# untitled.net
KiCad netlist of a schematic drawn in EAGLE
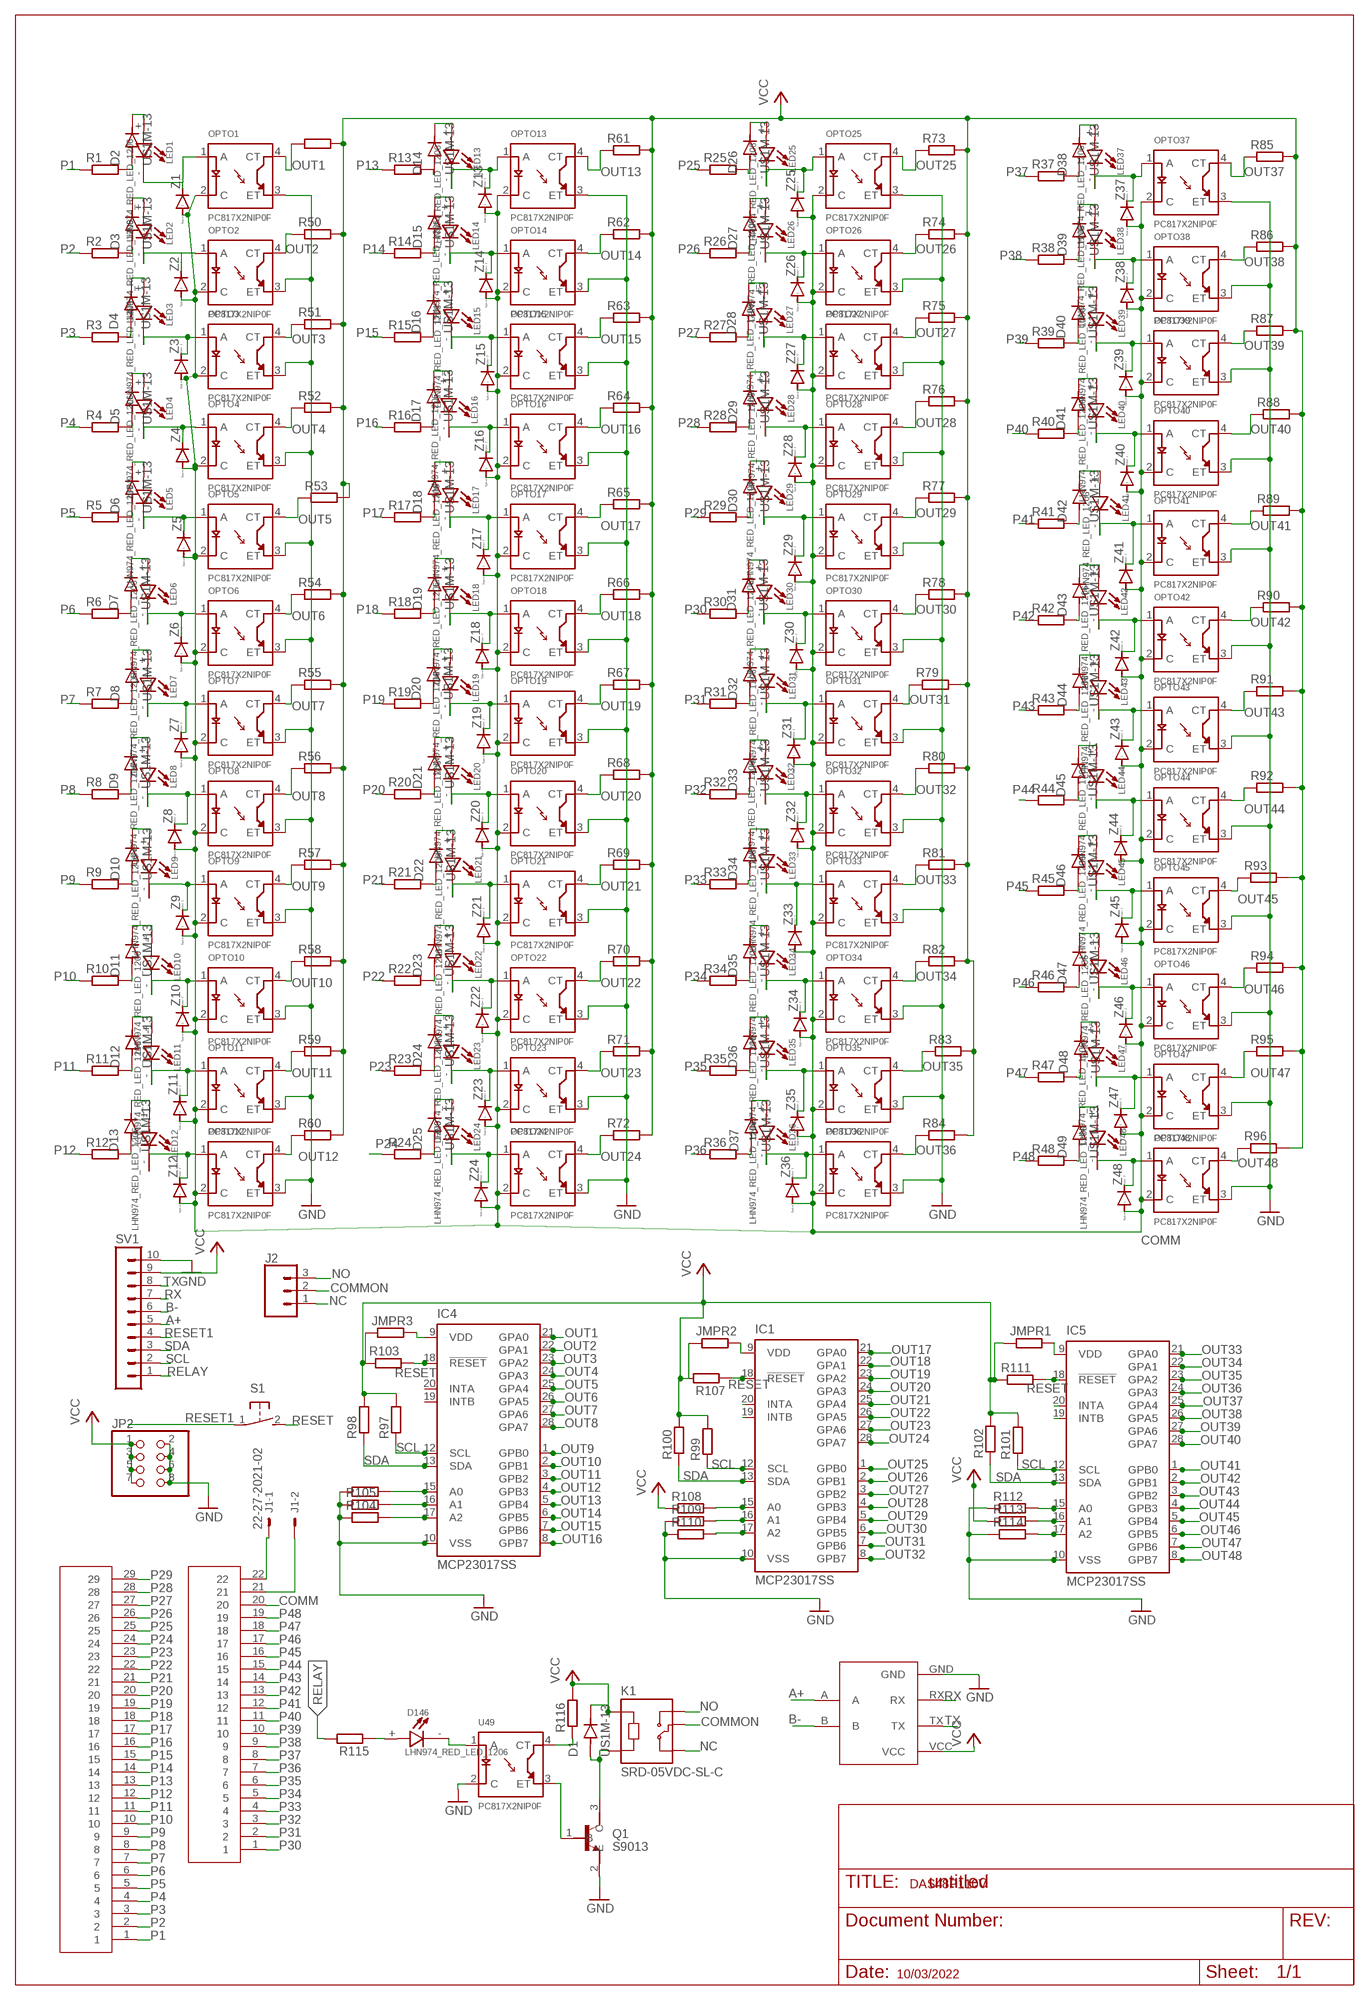
[diagram p0: schematic, sheet 1]

(export (version "E")
  (design (tool "Eeschema 10.0.6"))
  (components
    (comp (ref "D1")
      (value "US1M-13")
      (footprint "eagle-import:DIOM5226X240N")
      (fields (field (name "MF") "Diodes Incorporated"))
      (libsource (lib "eagle-import") (part "US1M-13"))
    )
    (comp (ref "D2")
      (value "US1M-13")
      (footprint "eagle-import:DIOM5226X240N")
      (fields (field (name "MF") "Diodes Incorporated"))
      (libsource (lib "eagle-import") (part "US1M-13"))
    )
    (comp (ref "D3")
      (value "US1M-13")
      (footprint "eagle-import:DIOM5226X240N")
      (fields (field (name "MF") "Diodes Incorporated"))
      (libsource (lib "eagle-import") (part "US1M-13"))
    )
    (comp (ref "D4")
      (value "US1M-13")
      (footprint "eagle-import:DIOM5226X240N")
      (fields (field (name "MF") "Diodes Incorporated"))
      (libsource (lib "eagle-import") (part "US1M-13"))
    )
    (comp (ref "D5")
      (value "US1M-13")
      (footprint "eagle-import:DIOM5226X240N")
      (fields (field (name "MF") "Diodes Incorporated"))
      (libsource (lib "eagle-import") (part "US1M-13"))
    )
    (comp (ref "D6")
      (value "US1M-13")
      (footprint "eagle-import:DIOM5226X240N")
      (fields (field (name "MF") "Diodes Incorporated"))
      (libsource (lib "eagle-import") (part "US1M-13"))
    )
    (comp (ref "D7")
      (value "US1M-13")
      (footprint "eagle-import:DIOM5226X240N")
      (fields (field (name "MF") "Diodes Incorporated"))
      (libsource (lib "eagle-import") (part "US1M-13"))
    )
    (comp (ref "D8")
      (value "US1M-13")
      (footprint "eagle-import:DIOM5226X240N")
      (fields (field (name "MF") "Diodes Incorporated"))
      (libsource (lib "eagle-import") (part "US1M-13"))
    )
    (comp (ref "D9")
      (value "US1M-13")
      (footprint "eagle-import:DIOM5226X240N")
      (fields (field (name "MF") "Diodes Incorporated"))
      (libsource (lib "eagle-import") (part "US1M-13"))
    )
    (comp (ref "D10")
      (value "US1M-13")
      (footprint "eagle-import:DIOM5226X240N")
      (fields (field (name "MF") "Diodes Incorporated"))
      (libsource (lib "eagle-import") (part "US1M-13"))
    )
    (comp (ref "D11")
      (value "US1M-13")
      (footprint "eagle-import:DIOM5226X240N")
      (fields (field (name "MF") "Diodes Incorporated"))
      (libsource (lib "eagle-import") (part "US1M-13"))
    )
    (comp (ref "D12")
      (value "US1M-13")
      (footprint "eagle-import:DIOM5226X240N")
      (fields (field (name "MF") "Diodes Incorporated"))
      (libsource (lib "eagle-import") (part "US1M-13"))
    )
    (comp (ref "D13")
      (value "US1M-13")
      (footprint "eagle-import:DIOM5226X240N")
      (fields (field (name "MF") "Diodes Incorporated"))
      (libsource (lib "eagle-import") (part "US1M-13"))
    )
    (comp (ref "D14")
      (value "US1M-13")
      (footprint "eagle-import:DIOM5226X240N")
      (fields (field (name "MF") "Diodes Incorporated"))
      (libsource (lib "eagle-import") (part "US1M-13"))
    )
    (comp (ref "D15")
      (value "US1M-13")
      (footprint "eagle-import:DIOM5226X240N")
      (fields (field (name "MF") "Diodes Incorporated"))
      (libsource (lib "eagle-import") (part "US1M-13"))
    )
    (comp (ref "D16")
      (value "US1M-13")
      (footprint "eagle-import:DIOM5226X240N")
      (fields (field (name "MF") "Diodes Incorporated"))
      (libsource (lib "eagle-import") (part "US1M-13"))
    )
    (comp (ref "D17")
      (value "US1M-13")
      (footprint "eagle-import:DIOM5226X240N")
      (fields (field (name "MF") "Diodes Incorporated"))
      (libsource (lib "eagle-import") (part "US1M-13"))
    )
    (comp (ref "D18")
      (value "US1M-13")
      (footprint "eagle-import:DIOM5226X240N")
      (fields (field (name "MF") "Diodes Incorporated"))
      (libsource (lib "eagle-import") (part "US1M-13"))
    )
    (comp (ref "D19")
      (value "US1M-13")
      (footprint "eagle-import:DIOM5226X240N")
      (fields (field (name "MF") "Diodes Incorporated"))
      (libsource (lib "eagle-import") (part "US1M-13"))
    )
    (comp (ref "D20")
      (value "US1M-13")
      (footprint "eagle-import:DIOM5226X240N")
      (fields (field (name "MF") "Diodes Incorporated"))
      (libsource (lib "eagle-import") (part "US1M-13"))
    )
    (comp (ref "D21")
      (value "US1M-13")
      (footprint "eagle-import:DIOM5226X240N")
      (fields (field (name "MF") "Diodes Incorporated"))
      (libsource (lib "eagle-import") (part "US1M-13"))
    )
    (comp (ref "D22")
      (value "US1M-13")
      (footprint "eagle-import:DIOM5226X240N")
      (fields (field (name "MF") "Diodes Incorporated"))
      (libsource (lib "eagle-import") (part "US1M-13"))
    )
    (comp (ref "D23")
      (value "US1M-13")
      (footprint "eagle-import:DIOM5226X240N")
      (fields (field (name "MF") "Diodes Incorporated"))
      (libsource (lib "eagle-import") (part "US1M-13"))
    )
    (comp (ref "D24")
      (value "US1M-13")
      (footprint "eagle-import:DIOM5226X240N")
      (fields (field (name "MF") "Diodes Incorporated"))
      (libsource (lib "eagle-import") (part "US1M-13"))
    )
    (comp (ref "D25")
      (value "US1M-13")
      (footprint "eagle-import:DIOM5226X240N")
      (fields (field (name "MF") "Diodes Incorporated"))
      (libsource (lib "eagle-import") (part "US1M-13"))
    )
    (comp (ref "D26")
      (value "US1M-13")
      (footprint "eagle-import:DIOM5226X240N")
      (fields (field (name "MF") "Diodes Incorporated"))
      (libsource (lib "eagle-import") (part "US1M-13"))
    )
    (comp (ref "D27")
      (value "US1M-13")
      (footprint "eagle-import:DIOM5226X240N")
      (fields (field (name "MF") "Diodes Incorporated"))
      (libsource (lib "eagle-import") (part "US1M-13"))
    )
    (comp (ref "D28")
      (value "US1M-13")
      (footprint "eagle-import:DIOM5226X240N")
      (fields (field (name "MF") "Diodes Incorporated"))
      (libsource (lib "eagle-import") (part "US1M-13"))
    )
    (comp (ref "D29")
      (value "US1M-13")
      (footprint "eagle-import:DIOM5226X240N")
      (fields (field (name "MF") "Diodes Incorporated"))
      (libsource (lib "eagle-import") (part "US1M-13"))
    )
    (comp (ref "D30")
      (value "US1M-13")
      (footprint "eagle-import:DIOM5226X240N")
      (fields (field (name "MF") "Diodes Incorporated"))
      (libsource (lib "eagle-import") (part "US1M-13"))
    )
    (comp (ref "D31")
      (value "US1M-13")
      (footprint "eagle-import:DIOM5226X240N")
      (fields (field (name "MF") "Diodes Incorporated"))
      (libsource (lib "eagle-import") (part "US1M-13"))
    )
    (comp (ref "D32")
      (value "US1M-13")
      (footprint "eagle-import:DIOM5226X240N")
      (fields (field (name "MF") "Diodes Incorporated"))
      (libsource (lib "eagle-import") (part "US1M-13"))
    )
    (comp (ref "D33")
      (value "US1M-13")
      (footprint "eagle-import:DIOM5226X240N")
      (fields (field (name "MF") "Diodes Incorporated"))
      (libsource (lib "eagle-import") (part "US1M-13"))
    )
    (comp (ref "D34")
      (value "US1M-13")
      (footprint "eagle-import:DIOM5226X240N")
      (fields (field (name "MF") "Diodes Incorporated"))
      (libsource (lib "eagle-import") (part "US1M-13"))
    )
    (comp (ref "D35")
      (value "US1M-13")
      (footprint "eagle-import:DIOM5226X240N")
      (fields (field (name "MF") "Diodes Incorporated"))
      (libsource (lib "eagle-import") (part "US1M-13"))
    )
    (comp (ref "D36")
      (value "US1M-13")
      (footprint "eagle-import:DIOM5226X240N")
      (fields (field (name "MF") "Diodes Incorporated"))
      (libsource (lib "eagle-import") (part "US1M-13"))
    )
    (comp (ref "D37")
      (value "US1M-13")
      (footprint "eagle-import:DIOM5226X240N")
      (fields (field (name "MF") "Diodes Incorporated"))
      (libsource (lib "eagle-import") (part "US1M-13"))
    )
    (comp (ref "D38")
      (value "US1M-13")
      (footprint "eagle-import:DIOM5226X240N")
      (fields (field (name "MF") "Diodes Incorporated"))
      (libsource (lib "eagle-import") (part "US1M-13"))
    )
    (comp (ref "D39")
      (value "US1M-13")
      (footprint "eagle-import:DIOM5226X240N")
      (fields (field (name "MF") "Diodes Incorporated"))
      (libsource (lib "eagle-import") (part "US1M-13"))
    )
    (comp (ref "D40")
      (value "US1M-13")
      (footprint "eagle-import:DIOM5226X240N")
      (fields (field (name "MF") "Diodes Incorporated"))
      (libsource (lib "eagle-import") (part "US1M-13"))
    )
    (comp (ref "D41")
      (value "US1M-13")
      (footprint "eagle-import:DIOM5226X240N")
      (fields (field (name "MF") "Diodes Incorporated"))
      (libsource (lib "eagle-import") (part "US1M-13"))
    )
    (comp (ref "D42")
      (value "US1M-13")
      (footprint "eagle-import:DIOM5226X240N")
      (fields (field (name "MF") "Diodes Incorporated"))
      (libsource (lib "eagle-import") (part "US1M-13"))
    )
    (comp (ref "D43")
      (value "US1M-13")
      (footprint "eagle-import:DIOM5226X240N")
      (fields (field (name "MF") "Diodes Incorporated"))
      (libsource (lib "eagle-import") (part "US1M-13"))
    )
    (comp (ref "D44")
      (value "US1M-13")
      (footprint "eagle-import:DIOM5226X240N")
      (fields (field (name "MF") "Diodes Incorporated"))
      (libsource (lib "eagle-import") (part "US1M-13"))
    )
    (comp (ref "D45")
      (value "US1M-13")
      (footprint "eagle-import:DIOM5226X240N")
      (fields (field (name "MF") "Diodes Incorporated"))
      (libsource (lib "eagle-import") (part "US1M-13"))
    )
    (comp (ref "D46")
      (value "US1M-13")
      (footprint "eagle-import:DIOM5226X240N")
      (fields (field (name "MF") "Diodes Incorporated"))
      (libsource (lib "eagle-import") (part "US1M-13"))
    )
    (comp (ref "D47")
      (value "US1M-13")
      (footprint "eagle-import:DIOM5226X240N")
      (fields (field (name "MF") "Diodes Incorporated"))
      (libsource (lib "eagle-import") (part "US1M-13"))
    )
    (comp (ref "D48")
      (value "US1M-13")
      (footprint "eagle-import:DIOM5226X240N")
      (fields (field (name "MF") "Diodes Incorporated"))
      (libsource (lib "eagle-import") (part "US1M-13"))
    )
    (comp (ref "D49")
      (value "US1M-13")
      (footprint "eagle-import:DIOM5226X240N")
      (fields (field (name "MF") "Diodes Incorporated"))
      (libsource (lib "eagle-import") (part "US1M-13"))
    )
    (comp (ref "D146")
      (value "LHN974_RED_LED_1206")
      (footprint "eagle-import:LEDC3216X120N")
      (fields (field (name "MF") "Osram") (field (name "MP") "LHN974 RED LED 1206"))
      (libsource (lib "eagle-import") (part "LHN974_RED_LED_1206"))
    )
    (comp (ref "HEADER-22P1")
      (value "HEADER-22P")
      (footprint "eagle-import:HEADER-29P")
      (libsource (lib "eagle-import") (part "HEADER-22P"))
    )
    (comp (ref "HEADER-29P1")
      (value "HEADER-29P")
      (footprint "eagle-import:HEADER-29P")
      (libsource (lib "eagle-import") (part "HEADER-29P"))
    )
    (comp (ref "IC1")
      (value "MCP23017SS")
      (footprint "eagle-import:SSOP28DB")
      (libsource (lib "eagle-import") (part "MCP23017SS"))
    )
    (comp (ref "IC4")
      (value "MCP23017SS")
      (footprint "eagle-import:SSOP28DB")
      (libsource (lib "eagle-import") (part "MCP23017SS"))
    )
    (comp (ref "IC5")
      (value "MCP23017SS")
      (footprint "eagle-import:SSOP28DB")
      (libsource (lib "eagle-import") (part "MCP23017SS"))
    )
    (comp (ref "J1")
      (value "22-27-2021-02")
      (footprint "eagle-import:6410-02")
      (fields (field (name "MF") "MOLEX"))
      (libsource (lib "eagle-import") (part "22-?-0227-2021"))
    )
    (comp (ref "J2")
      (value "CONN_03LONGPADS")
      (footprint "eagle-import:1X03_LONGPADS")
      (libsource (lib "eagle-import") (part "CONN_03LONGPADS"))
    )
    (comp (ref "JMPR1")
      (value "R-EU_R0402")
      (footprint "eagle-import:R0402")
      (libsource (lib "eagle-import") (part "R-EU_R0402"))
    )
    (comp (ref "JMPR2")
      (value "R-EU_R0402")
      (footprint "eagle-import:R0402")
      (libsource (lib "eagle-import") (part "R-EU_R0402"))
    )
    (comp (ref "JMPR3")
      (value "R-EU_R0402")
      (footprint "eagle-import:R0402")
      (libsource (lib "eagle-import") (part "R-EU_R0402"))
    )
    (comp (ref "JP2")
      (value "PINHD-2X4")
      (footprint "eagle-import:2X04")
      (libsource (lib "eagle-import") (part "PINHD-2X4"))
    )
    (comp (ref "K1")
      (value "SRD-05VDC-SL-C")
      (footprint "eagle-import:RELAY_SRD-05VDC-SL-C")
      (fields (field (name "MF") "Songle Relay"))
      (libsource (lib "eagle-import") (part "SRD-05VDC-SL-C"))
    )
    (comp (ref "LED1")
      (value "LHN974_RED_LED_1206")
      (footprint "eagle-import:LEDC3216X120N")
      (fields (field (name "MF") "Osram") (field (name "MP") "LHN974 RED LED 1206"))
      (libsource (lib "eagle-import") (part "LHN974_RED_LED_1206"))
    )
    (comp (ref "LED2")
      (value "LHN974_RED_LED_1206")
      (footprint "eagle-import:LEDC3216X120N")
      (fields (field (name "MF") "Osram") (field (name "MP") "LHN974 RED LED 1206"))
      (libsource (lib "eagle-import") (part "LHN974_RED_LED_1206"))
    )
    (comp (ref "LED3")
      (value "LHN974_RED_LED_1206")
      (footprint "eagle-import:LEDC3216X120N")
      (fields (field (name "MF") "Osram") (field (name "MP") "LHN974 RED LED 1206"))
      (libsource (lib "eagle-import") (part "LHN974_RED_LED_1206"))
    )
    (comp (ref "LED4")
      (value "LHN974_RED_LED_1206")
      (footprint "eagle-import:LEDC3216X120N")
      (fields (field (name "MF") "Osram") (field (name "MP") "LHN974 RED LED 1206"))
      (libsource (lib "eagle-import") (part "LHN974_RED_LED_1206"))
    )
    (comp (ref "LED5")
      (value "LHN974_RED_LED_1206")
      (footprint "eagle-import:LEDC3216X120N")
      (fields (field (name "MF") "Osram") (field (name "MP") "LHN974 RED LED 1206"))
      (libsource (lib "eagle-import") (part "LHN974_RED_LED_1206"))
    )
    (comp (ref "LED6")
      (value "LHN974_RED_LED_1206")
      (footprint "eagle-import:LEDC3216X120N")
      (fields (field (name "MF") "Osram") (field (name "MP") "LHN974 RED LED 1206"))
      (libsource (lib "eagle-import") (part "LHN974_RED_LED_1206"))
    )
    (comp (ref "LED7")
      (value "LHN974_RED_LED_1206")
      (footprint "eagle-import:LEDC3216X120N")
      (fields (field (name "MF") "Osram") (field (name "MP") "LHN974 RED LED 1206"))
      (libsource (lib "eagle-import") (part "LHN974_RED_LED_1206"))
    )
    (comp (ref "LED8")
      (value "LHN974_RED_LED_1206")
      (footprint "eagle-import:LEDC3216X120N")
      (fields (field (name "MF") "Osram") (field (name "MP") "LHN974 RED LED 1206"))
      (libsource (lib "eagle-import") (part "LHN974_RED_LED_1206"))
    )
    (comp (ref "LED9")
      (value "LHN974_RED_LED_1206")
      (footprint "eagle-import:LEDC3216X120N")
      (fields (field (name "MF") "Osram") (field (name "MP") "LHN974 RED LED 1206"))
      (libsource (lib "eagle-import") (part "LHN974_RED_LED_1206"))
    )
    (comp (ref "LED10")
      (value "LHN974_RED_LED_1206")
      (footprint "eagle-import:LEDC3216X120N")
      (fields (field (name "MF") "Osram") (field (name "MP") "LHN974 RED LED 1206"))
      (libsource (lib "eagle-import") (part "LHN974_RED_LED_1206"))
    )
    (comp (ref "LED11")
      (value "LHN974_RED_LED_1206")
      (footprint "eagle-import:LEDC3216X120N")
      (fields (field (name "MF") "Osram") (field (name "MP") "LHN974 RED LED 1206"))
      (libsource (lib "eagle-import") (part "LHN974_RED_LED_1206"))
    )
    (comp (ref "LED12")
      (value "LHN974_RED_LED_1206")
      (footprint "eagle-import:LEDC3216X120N")
      (fields (field (name "MF") "Osram") (field (name "MP") "LHN974 RED LED 1206"))
      (libsource (lib "eagle-import") (part "LHN974_RED_LED_1206"))
    )
    (comp (ref "LED13")
      (value "LHN974_RED_LED_1206")
      (footprint "eagle-import:LEDC3216X120N")
      (fields (field (name "MF") "Osram") (field (name "MP") "LHN974 RED LED 1206"))
      (libsource (lib "eagle-import") (part "LHN974_RED_LED_1206"))
    )
    (comp (ref "LED14")
      (value "LHN974_RED_LED_1206")
      (footprint "eagle-import:LEDC3216X120N")
      (fields (field (name "MF") "Osram") (field (name "MP") "LHN974 RED LED 1206"))
      (libsource (lib "eagle-import") (part "LHN974_RED_LED_1206"))
    )
    (comp (ref "LED15")
      (value "LHN974_RED_LED_1206")
      (footprint "eagle-import:LEDC3216X120N")
      (fields (field (name "MF") "Osram") (field (name "MP") "LHN974 RED LED 1206"))
      (libsource (lib "eagle-import") (part "LHN974_RED_LED_1206"))
    )
    (comp (ref "LED16")
      (value "LHN974_RED_LED_1206")
      (footprint "eagle-import:LEDC3216X120N")
      (fields (field (name "MF") "Osram") (field (name "MP") "LHN974 RED LED 1206"))
      (libsource (lib "eagle-import") (part "LHN974_RED_LED_1206"))
    )
    (comp (ref "LED17")
      (value "LHN974_RED_LED_1206")
      (footprint "eagle-import:LEDC3216X120N")
      (fields (field (name "MF") "Osram") (field (name "MP") "LHN974 RED LED 1206"))
      (libsource (lib "eagle-import") (part "LHN974_RED_LED_1206"))
    )
    (comp (ref "LED18")
      (value "LHN974_RED_LED_1206")
      (footprint "eagle-import:LEDC3216X120N")
      (fields (field (name "MF") "Osram") (field (name "MP") "LHN974 RED LED 1206"))
      (libsource (lib "eagle-import") (part "LHN974_RED_LED_1206"))
    )
    (comp (ref "LED19")
      (value "LHN974_RED_LED_1206")
      (footprint "eagle-import:LEDC3216X120N")
      (fields (field (name "MF") "Osram") (field (name "MP") "LHN974 RED LED 1206"))
      (libsource (lib "eagle-import") (part "LHN974_RED_LED_1206"))
    )
    (comp (ref "LED20")
      (value "LHN974_RED_LED_1206")
      (footprint "eagle-import:LEDC3216X120N")
      (fields (field (name "MF") "Osram") (field (name "MP") "LHN974 RED LED 1206"))
      (libsource (lib "eagle-import") (part "LHN974_RED_LED_1206"))
    )
    (comp (ref "LED21")
      (value "LHN974_RED_LED_1206")
      (footprint "eagle-import:LEDC3216X120N")
      (fields (field (name "MF") "Osram") (field (name "MP") "LHN974 RED LED 1206"))
      (libsource (lib "eagle-import") (part "LHN974_RED_LED_1206"))
    )
    (comp (ref "LED22")
      (value "LHN974_RED_LED_1206")
      (footprint "eagle-import:LEDC3216X120N")
      (fields (field (name "MF") "Osram") (field (name "MP") "LHN974 RED LED 1206"))
      (libsource (lib "eagle-import") (part "LHN974_RED_LED_1206"))
    )
    (comp (ref "LED23")
      (value "LHN974_RED_LED_1206")
      (footprint "eagle-import:LEDC3216X120N")
      (fields (field (name "MF") "Osram") (field (name "MP") "LHN974 RED LED 1206"))
      (libsource (lib "eagle-import") (part "LHN974_RED_LED_1206"))
    )
    (comp (ref "LED24")
      (value "LHN974_RED_LED_1206")
      (footprint "eagle-import:LEDC3216X120N")
      (fields (field (name "MF") "Osram") (field (name "MP") "LHN974 RED LED 1206"))
      (libsource (lib "eagle-import") (part "LHN974_RED_LED_1206"))
    )
    (comp (ref "LED25")
      (value "LHN974_RED_LED_1206")
      (footprint "eagle-import:LEDC3216X120N")
      (fields (field (name "MF") "Osram") (field (name "MP") "LHN974 RED LED 1206"))
      (libsource (lib "eagle-import") (part "LHN974_RED_LED_1206"))
    )
    (comp (ref "LED26")
      (value "LHN974_RED_LED_1206")
      (footprint "eagle-import:LEDC3216X120N")
      (fields (field (name "MF") "Osram") (field (name "MP") "LHN974 RED LED 1206"))
      (libsource (lib "eagle-import") (part "LHN974_RED_LED_1206"))
    )
    (comp (ref "LED27")
      (value "LHN974_RED_LED_1206")
      (footprint "eagle-import:LEDC3216X120N")
      (fields (field (name "MF") "Osram") (field (name "MP") "LHN974 RED LED 1206"))
      (libsource (lib "eagle-import") (part "LHN974_RED_LED_1206"))
    )
    (comp (ref "LED28")
      (value "LHN974_RED_LED_1206")
      (footprint "eagle-import:LEDC3216X120N")
      (fields (field (name "MF") "Osram") (field (name "MP") "LHN974 RED LED 1206"))
      (libsource (lib "eagle-import") (part "LHN974_RED_LED_1206"))
    )
    (comp (ref "LED29")
      (value "LHN974_RED_LED_1206")
      (footprint "eagle-import:LEDC3216X120N")
      (fields (field (name "MF") "Osram") (field (name "MP") "LHN974 RED LED 1206"))
      (libsource (lib "eagle-import") (part "LHN974_RED_LED_1206"))
    )
    (comp (ref "LED30")
      (value "LHN974_RED_LED_1206")
      (footprint "eagle-import:LEDC3216X120N")
      (fields (field (name "MF") "Osram") (field (name "MP") "LHN974 RED LED 1206"))
      (libsource (lib "eagle-import") (part "LHN974_RED_LED_1206"))
    )
    (comp (ref "LED31")
      (value "LHN974_RED_LED_1206")
      (footprint "eagle-import:LEDC3216X120N")
      (fields (field (name "MF") "Osram") (field (name "MP") "LHN974 RED LED 1206"))
      (libsource (lib "eagle-import") (part "LHN974_RED_LED_1206"))
    )
    (comp (ref "LED32")
      (value "LHN974_RED_LED_1206")
      (footprint "eagle-import:LEDC3216X120N")
      (fields (field (name "MF") "Osram") (field (name "MP") "LHN974 RED LED 1206"))
      (libsource (lib "eagle-import") (part "LHN974_RED_LED_1206"))
    )
    (comp (ref "LED33")
      (value "LHN974_RED_LED_1206")
      (footprint "eagle-import:LEDC3216X120N")
      (fields (field (name "MF") "Osram") (field (name "MP") "LHN974 RED LED 1206"))
      (libsource (lib "eagle-import") (part "LHN974_RED_LED_1206"))
    )
    (comp (ref "LED34")
      (value "LHN974_RED_LED_1206")
      (footprint "eagle-import:LEDC3216X120N")
      (fields (field (name "MF") "Osram") (field (name "MP") "LHN974 RED LED 1206"))
      (libsource (lib "eagle-import") (part "LHN974_RED_LED_1206"))
    )
    (comp (ref "LED35")
      (value "LHN974_RED_LED_1206")
      (footprint "eagle-import:LEDC3216X120N")
      (fields (field (name "MF") "Osram") (field (name "MP") "LHN974 RED LED 1206"))
      (libsource (lib "eagle-import") (part "LHN974_RED_LED_1206"))
    )
    (comp (ref "LED36")
      (value "LHN974_RED_LED_1206")
      (footprint "eagle-import:LEDC3216X120N")
      (fields (field (name "MF") "Osram") (field (name "MP") "LHN974 RED LED 1206"))
      (libsource (lib "eagle-import") (part "LHN974_RED_LED_1206"))
    )
    (comp (ref "LED37")
      (value "LHN974_RED_LED_1206")
      (footprint "eagle-import:LEDC3216X120N")
      (fields (field (name "MF") "Osram") (field (name "MP") "LHN974 RED LED 1206"))
      (libsource (lib "eagle-import") (part "LHN974_RED_LED_1206"))
    )
    (comp (ref "LED38")
      (value "LHN974_RED_LED_1206")
      (footprint "eagle-import:LEDC3216X120N")
      (fields (field (name "MF") "Osram") (field (name "MP") "LHN974 RED LED 1206"))
      (libsource (lib "eagle-import") (part "LHN974_RED_LED_1206"))
    )
    (comp (ref "LED39")
      (value "LHN974_RED_LED_1206")
      (footprint "eagle-import:LEDC3216X120N")
      (fields (field (name "MF") "Osram") (field (name "MP") "LHN974 RED LED 1206"))
      (libsource (lib "eagle-import") (part "LHN974_RED_LED_1206"))
    )
    (comp (ref "LED40")
      (value "LHN974_RED_LED_1206")
      (footprint "eagle-import:LEDC3216X120N")
      (fields (field (name "MF") "Osram") (field (name "MP") "LHN974 RED LED 1206"))
      (libsource (lib "eagle-import") (part "LHN974_RED_LED_1206"))
    )
    (comp (ref "LED41")
      (value "LHN974_RED_LED_1206")
      (footprint "eagle-import:LEDC3216X120N")
      (fields (field (name "MF") "Osram") (field (name "MP") "LHN974 RED LED 1206"))
      (libsource (lib "eagle-import") (part "LHN974_RED_LED_1206"))
    )
    (comp (ref "LED42")
      (value "LHN974_RED_LED_1206")
      (footprint "eagle-import:LEDC3216X120N")
      (fields (field (name "MF") "Osram") (field (name "MP") "LHN974 RED LED 1206"))
      (libsource (lib "eagle-import") (part "LHN974_RED_LED_1206"))
    )
    (comp (ref "LED43")
      (value "LHN974_RED_LED_1206")
      (footprint "eagle-import:LEDC3216X120N")
      (fields (field (name "MF") "Osram") (field (name "MP") "LHN974 RED LED 1206"))
      (libsource (lib "eagle-import") (part "LHN974_RED_LED_1206"))
    )
    (comp (ref "LED44")
      (value "LHN974_RED_LED_1206")
      (footprint "eagle-import:LEDC3216X120N")
      (fields (field (name "MF") "Osram") (field (name "MP") "LHN974 RED LED 1206"))
      (libsource (lib "eagle-import") (part "LHN974_RED_LED_1206"))
    )
    (comp (ref "LED45")
      (value "LHN974_RED_LED_1206")
      (footprint "eagle-import:LEDC3216X120N")
      (fields (field (name "MF") "Osram") (field (name "MP") "LHN974 RED LED 1206"))
      (libsource (lib "eagle-import") (part "LHN974_RED_LED_1206"))
    )
    (comp (ref "LED46")
      (value "LHN974_RED_LED_1206")
      (footprint "eagle-import:LEDC3216X120N")
      (fields (field (name "MF") "Osram") (field (name "MP") "LHN974 RED LED 1206"))
      (libsource (lib "eagle-import") (part "LHN974_RED_LED_1206"))
    )
    (comp (ref "LED47")
      (value "LHN974_RED_LED_1206")
      (footprint "eagle-import:LEDC3216X120N")
      (fields (field (name "MF") "Osram") (field (name "MP") "LHN974 RED LED 1206"))
      (libsource (lib "eagle-import") (part "LHN974_RED_LED_1206"))
    )
    (comp (ref "LED48")
      (value "LHN974_RED_LED_1206")
      (footprint "eagle-import:LEDC3216X120N")
      (fields (field (name "MF") "Osram") (field (name "MP") "LHN974 RED LED 1206"))
      (libsource (lib "eagle-import") (part "LHN974_RED_LED_1206"))
    )
    (comp (ref "OPTO1")
      (value "PC817X2NIP0F")
      (footprint "eagle-import:SOT254P975X400-4N")
      (fields (field (name "MF") "Sharp Microelectronics"))
      (libsource (lib "eagle-import") (part "PC817X2NIP0F"))
    )
    (comp (ref "OPTO2")
      (value "PC817X2NIP0F")
      (footprint "eagle-import:SOT254P975X400-4N")
      (fields (field (name "MF") "Sharp Microelectronics"))
      (libsource (lib "eagle-import") (part "PC817X2NIP0F"))
    )
    (comp (ref "OPTO3")
      (value "PC817X2NIP0F")
      (footprint "eagle-import:SOT254P975X400-4N")
      (fields (field (name "MF") "Sharp Microelectronics"))
      (libsource (lib "eagle-import") (part "PC817X2NIP0F"))
    )
    (comp (ref "OPTO4")
      (value "PC817X2NIP0F")
      (footprint "eagle-import:SOT254P975X400-4N")
      (fields (field (name "MF") "Sharp Microelectronics"))
      (libsource (lib "eagle-import") (part "PC817X2NIP0F"))
    )
    (comp (ref "OPTO5")
      (value "PC817X2NIP0F")
      (footprint "eagle-import:SOT254P975X400-4N")
      (fields (field (name "MF") "Sharp Microelectronics"))
      (libsource (lib "eagle-import") (part "PC817X2NIP0F"))
    )
    (comp (ref "OPTO6")
      (value "PC817X2NIP0F")
      (footprint "eagle-import:SOT254P975X400-4N")
      (fields (field (name "MF") "Sharp Microelectronics"))
      (libsource (lib "eagle-import") (part "PC817X2NIP0F"))
    )
    (comp (ref "OPTO7")
      (value "PC817X2NIP0F")
      (footprint "eagle-import:SOT254P975X400-4N")
      (fields (field (name "MF") "Sharp Microelectronics"))
      (libsource (lib "eagle-import") (part "PC817X2NIP0F"))
    )
    (comp (ref "OPTO8")
      (value "PC817X2NIP0F")
      (footprint "eagle-import:SOT254P975X400-4N")
      (fields (field (name "MF") "Sharp Microelectronics"))
      (libsource (lib "eagle-import") (part "PC817X2NIP0F"))
    )
    (comp (ref "OPTO9")
      (value "PC817X2NIP0F")
      (footprint "eagle-import:SOT254P975X400-4N")
      (fields (field (name "MF") "Sharp Microelectronics"))
      (libsource (lib "eagle-import") (part "PC817X2NIP0F"))
    )
    (comp (ref "OPTO10")
      (value "PC817X2NIP0F")
      (footprint "eagle-import:SOT254P975X400-4N")
      (fields (field (name "MF") "Sharp Microelectronics"))
      (libsource (lib "eagle-import") (part "PC817X2NIP0F"))
    )
    (comp (ref "OPTO11")
      (value "PC817X2NIP0F")
      (footprint "eagle-import:SOT254P975X400-4N")
      (fields (field (name "MF") "Sharp Microelectronics"))
      (libsource (lib "eagle-import") (part "PC817X2NIP0F"))
    )
    (comp (ref "OPTO12")
      (value "PC817X2NIP0F")
      (footprint "eagle-import:SOT254P975X400-4N")
      (fields (field (name "MF") "Sharp Microelectronics"))
      (libsource (lib "eagle-import") (part "PC817X2NIP0F"))
    )
    (comp (ref "OPTO13")
      (value "PC817X2NIP0F")
      (footprint "eagle-import:SOT254P975X400-4N")
      (fields (field (name "MF") "Sharp Microelectronics"))
      (libsource (lib "eagle-import") (part "PC817X2NIP0F"))
    )
    (comp (ref "OPTO14")
      (value "PC817X2NIP0F")
      (footprint "eagle-import:SOT254P975X400-4N")
      (fields (field (name "MF") "Sharp Microelectronics"))
      (libsource (lib "eagle-import") (part "PC817X2NIP0F"))
    )
    (comp (ref "OPTO15")
      (value "PC817X2NIP0F")
      (footprint "eagle-import:SOT254P975X400-4N")
      (fields (field (name "MF") "Sharp Microelectronics"))
      (libsource (lib "eagle-import") (part "PC817X2NIP0F"))
    )
    (comp (ref "OPTO16")
      (value "PC817X2NIP0F")
      (footprint "eagle-import:SOT254P975X400-4N")
      (fields (field (name "MF") "Sharp Microelectronics"))
      (libsource (lib "eagle-import") (part "PC817X2NIP0F"))
    )
    (comp (ref "OPTO17")
      (value "PC817X2NIP0F")
      (footprint "eagle-import:SOT254P975X400-4N")
      (fields (field (name "MF") "Sharp Microelectronics"))
      (libsource (lib "eagle-import") (part "PC817X2NIP0F"))
    )
    (comp (ref "OPTO18")
      (value "PC817X2NIP0F")
      (footprint "eagle-import:SOT254P975X400-4N")
      (fields (field (name "MF") "Sharp Microelectronics"))
      (libsource (lib "eagle-import") (part "PC817X2NIP0F"))
    )
    (comp (ref "OPTO19")
      (value "PC817X2NIP0F")
      (footprint "eagle-import:SOT254P975X400-4N")
      (fields (field (name "MF") "Sharp Microelectronics"))
      (libsource (lib "eagle-import") (part "PC817X2NIP0F"))
    )
    (comp (ref "OPTO20")
      (value "PC817X2NIP0F")
      (footprint "eagle-import:SOT254P975X400-4N")
      (fields (field (name "MF") "Sharp Microelectronics"))
      (libsource (lib "eagle-import") (part "PC817X2NIP0F"))
    )
    (comp (ref "OPTO21")
      (value "PC817X2NIP0F")
      (footprint "eagle-import:SOT254P975X400-4N")
      (fields (field (name "MF") "Sharp Microelectronics"))
      (libsource (lib "eagle-import") (part "PC817X2NIP0F"))
    )
    (comp (ref "OPTO22")
      (value "PC817X2NIP0F")
      (footprint "eagle-import:SOT254P975X400-4N")
      (fields (field (name "MF") "Sharp Microelectronics"))
      (libsource (lib "eagle-import") (part "PC817X2NIP0F"))
    )
    (comp (ref "OPTO23")
      (value "PC817X2NIP0F")
      (footprint "eagle-import:SOT254P975X400-4N")
      (fields (field (name "MF") "Sharp Microelectronics"))
      (libsource (lib "eagle-import") (part "PC817X2NIP0F"))
    )
    (comp (ref "OPTO24")
      (value "PC817X2NIP0F")
      (footprint "eagle-import:SOT254P975X400-4N")
      (fields (field (name "MF") "Sharp Microelectronics"))
      (libsource (lib "eagle-import") (part "PC817X2NIP0F"))
    )
    (comp (ref "OPTO25")
      (value "PC817X2NIP0F")
      (footprint "eagle-import:SOT254P975X400-4N")
      (fields (field (name "MF") "Sharp Microelectronics"))
      (libsource (lib "eagle-import") (part "PC817X2NIP0F"))
    )
    (comp (ref "OPTO26")
      (value "PC817X2NIP0F")
      (footprint "eagle-import:SOT254P975X400-4N")
      (fields (field (name "MF") "Sharp Microelectronics"))
      (libsource (lib "eagle-import") (part "PC817X2NIP0F"))
    )
    (comp (ref "OPTO27")
      (value "PC817X2NIP0F")
      (footprint "eagle-import:SOT254P975X400-4N")
      (fields (field (name "MF") "Sharp Microelectronics"))
      (libsource (lib "eagle-import") (part "PC817X2NIP0F"))
    )
    (comp (ref "OPTO28")
      (value "PC817X2NIP0F")
      (footprint "eagle-import:SOT254P975X400-4N")
      (fields (field (name "MF") "Sharp Microelectronics"))
      (libsource (lib "eagle-import") (part "PC817X2NIP0F"))
    )
    (comp (ref "OPTO29")
      (value "PC817X2NIP0F")
      (footprint "eagle-import:SOT254P975X400-4N")
      (fields (field (name "MF") "Sharp Microelectronics"))
      (libsource (lib "eagle-import") (part "PC817X2NIP0F"))
    )
    (comp (ref "OPTO30")
      (value "PC817X2NIP0F")
      (footprint "eagle-import:SOT254P975X400-4N")
      (fields (field (name "MF") "Sharp Microelectronics"))
      (libsource (lib "eagle-import") (part "PC817X2NIP0F"))
    )
    (comp (ref "OPTO31")
      (value "PC817X2NIP0F")
      (footprint "eagle-import:SOT254P975X400-4N")
      (fields (field (name "MF") "Sharp Microelectronics"))
      (libsource (lib "eagle-import") (part "PC817X2NIP0F"))
    )
    (comp (ref "OPTO32")
      (value "PC817X2NIP0F")
      (footprint "eagle-import:SOT254P975X400-4N")
      (fields (field (name "MF") "Sharp Microelectronics"))
      (libsource (lib "eagle-import") (part "PC817X2NIP0F"))
    )
    (comp (ref "OPTO33")
      (value "PC817X2NIP0F")
      (footprint "eagle-import:SOT254P975X400-4N")
      (fields (field (name "MF") "Sharp Microelectronics"))
      (libsource (lib "eagle-import") (part "PC817X2NIP0F"))
    )
    (comp (ref "OPTO34")
      (value "PC817X2NIP0F")
      (footprint "eagle-import:SOT254P975X400-4N")
      (fields (field (name "MF") "Sharp Microelectronics"))
      (libsource (lib "eagle-import") (part "PC817X2NIP0F"))
    )
    (comp (ref "OPTO35")
      (value "PC817X2NIP0F")
      (footprint "eagle-import:SOT254P975X400-4N")
      (fields (field (name "MF") "Sharp Microelectronics"))
      (libsource (lib "eagle-import") (part "PC817X2NIP0F"))
    )
    (comp (ref "OPTO36")
      (value "PC817X2NIP0F")
      (footprint "eagle-import:SOT254P975X400-4N")
      (fields (field (name "MF") "Sharp Microelectronics"))
      (libsource (lib "eagle-import") (part "PC817X2NIP0F"))
    )
    (comp (ref "OPTO37")
      (value "PC817X2NIP0F")
      (footprint "eagle-import:SOT254P975X400-4N")
      (fields (field (name "MF") "Sharp Microelectronics"))
      (libsource (lib "eagle-import") (part "PC817X2NIP0F"))
    )
    (comp (ref "OPTO38")
      (value "PC817X2NIP0F")
      (footprint "eagle-import:SOT254P975X400-4N")
      (fields (field (name "MF") "Sharp Microelectronics"))
      (libsource (lib "eagle-import") (part "PC817X2NIP0F"))
    )
    (comp (ref "OPTO39")
      (value "PC817X2NIP0F")
      (footprint "eagle-import:SOT254P975X400-4N")
      (fields (field (name "MF") "Sharp Microelectronics"))
      (libsource (lib "eagle-import") (part "PC817X2NIP0F"))
    )
    (comp (ref "OPTO40")
      (value "PC817X2NIP0F")
      (footprint "eagle-import:SOT254P975X400-4N")
      (fields (field (name "MF") "Sharp Microelectronics"))
      (libsource (lib "eagle-import") (part "PC817X2NIP0F"))
    )
    (comp (ref "OPTO41")
      (value "PC817X2NIP0F")
      (footprint "eagle-import:SOT254P975X400-4N")
      (fields (field (name "MF") "Sharp Microelectronics"))
      (libsource (lib "eagle-import") (part "PC817X2NIP0F"))
    )
    (comp (ref "OPTO42")
      (value "PC817X2NIP0F")
      (footprint "eagle-import:SOT254P975X400-4N")
      (fields (field (name "MF") "Sharp Microelectronics"))
      (libsource (lib "eagle-import") (part "PC817X2NIP0F"))
    )
    (comp (ref "OPTO43")
      (value "PC817X2NIP0F")
      (footprint "eagle-import:SOT254P975X400-4N")
      (fields (field (name "MF") "Sharp Microelectronics"))
      (libsource (lib "eagle-import") (part "PC817X2NIP0F"))
    )
    (comp (ref "OPTO44")
      (value "PC817X2NIP0F")
      (footprint "eagle-import:SOT254P975X400-4N")
      (fields (field (name "MF") "Sharp Microelectronics"))
      (libsource (lib "eagle-import") (part "PC817X2NIP0F"))
    )
    (comp (ref "OPTO45")
      (value "PC817X2NIP0F")
      (footprint "eagle-import:SOT254P975X400-4N")
      (fields (field (name "MF") "Sharp Microelectronics"))
      (libsource (lib "eagle-import") (part "PC817X2NIP0F"))
    )
    (comp (ref "OPTO46")
      (value "PC817X2NIP0F")
      (footprint "eagle-import:SOT254P975X400-4N")
      (fields (field (name "MF") "Sharp Microelectronics"))
      (libsource (lib "eagle-import") (part "PC817X2NIP0F"))
    )
    (comp (ref "OPTO47")
      (value "PC817X2NIP0F")
      (footprint "eagle-import:SOT254P975X400-4N")
      (fields (field (name "MF") "Sharp Microelectronics"))
      (libsource (lib "eagle-import") (part "PC817X2NIP0F"))
    )
    (comp (ref "OPTO48")
      (value "PC817X2NIP0F")
      (footprint "eagle-import:SOT254P975X400-4N")
      (fields (field (name "MF") "Sharp Microelectronics"))
      (libsource (lib "eagle-import") (part "PC817X2NIP0F"))
    )
    (comp (ref "Q1")
      (value "S9013")
      (footprint "eagle-import:SOT95P240X120-3N")
      (fields (field (name "MF") "JCET"))
      (libsource (lib "eagle-import") (part "S9013"))
    )
    (comp (ref "R1")
      (value "R-EU_0617/17")
      (footprint "eagle-import:0617_17")
      (libsource (lib "eagle-import") (part "R-EU_0617/17"))
    )
    (comp (ref "R2")
      (value "R-EU_0617/17")
      (footprint "eagle-import:0617_17")
      (libsource (lib "eagle-import") (part "R-EU_0617/17"))
    )
    (comp (ref "R3")
      (value "R-EU_0617/17")
      (footprint "eagle-import:0617_17")
      (libsource (lib "eagle-import") (part "R-EU_0617/17"))
    )
    (comp (ref "R4")
      (value "R-EU_0617/17")
      (footprint "eagle-import:0617_17")
      (libsource (lib "eagle-import") (part "R-EU_0617/17"))
    )
    (comp (ref "R5")
      (value "R-EU_0617/17")
      (footprint "eagle-import:0617_17")
      (libsource (lib "eagle-import") (part "R-EU_0617/17"))
    )
    (comp (ref "R6")
      (value "R-EU_0617/17")
      (footprint "eagle-import:0617_17")
      (libsource (lib "eagle-import") (part "R-EU_0617/17"))
    )
    (comp (ref "R7")
      (value "R-EU_0617/17")
      (footprint "eagle-import:0617_17")
      (libsource (lib "eagle-import") (part "R-EU_0617/17"))
    )
    (comp (ref "R8")
      (value "R-EU_0617/17")
      (footprint "eagle-import:0617_17")
      (libsource (lib "eagle-import") (part "R-EU_0617/17"))
    )
    (comp (ref "R9")
      (value "R-EU_0617/17")
      (footprint "eagle-import:0617_17")
      (libsource (lib "eagle-import") (part "R-EU_0617/17"))
    )
    (comp (ref "R10")
      (value "R-EU_0617/17")
      (footprint "eagle-import:0617_17")
      (libsource (lib "eagle-import") (part "R-EU_0617/17"))
    )
    (comp (ref "R11")
      (value "R-EU_0617/17")
      (footprint "eagle-import:0617_17")
      (libsource (lib "eagle-import") (part "R-EU_0617/17"))
    )
    (comp (ref "R12")
      (value "R-EU_0617/17")
      (footprint "eagle-import:0617_17")
      (libsource (lib "eagle-import") (part "R-EU_0617/17"))
    )
    (comp (ref "R13")
      (value "R-EU_0617/17")
      (footprint "eagle-import:0617_17")
      (libsource (lib "eagle-import") (part "R-EU_0617/17"))
    )
    (comp (ref "R14")
      (value "R-EU_0617/17")
      (footprint "eagle-import:0617_17")
      (libsource (lib "eagle-import") (part "R-EU_0617/17"))
    )
    (comp (ref "R15")
      (value "R-EU_0617/17")
      (footprint "eagle-import:0617_17")
      (libsource (lib "eagle-import") (part "R-EU_0617/17"))
    )
    (comp (ref "R16")
      (value "R-EU_0617/17")
      (footprint "eagle-import:0617_17")
      (libsource (lib "eagle-import") (part "R-EU_0617/17"))
    )
    (comp (ref "R17")
      (value "R-EU_0617/17")
      (footprint "eagle-import:0617_17")
      (libsource (lib "eagle-import") (part "R-EU_0617/17"))
    )
    (comp (ref "R18")
      (value "R-EU_0617/17")
      (footprint "eagle-import:0617_17")
      (libsource (lib "eagle-import") (part "R-EU_0617/17"))
    )
    (comp (ref "R19")
      (value "R-EU_0617/17")
      (footprint "eagle-import:0617_17")
      (libsource (lib "eagle-import") (part "R-EU_0617/17"))
    )
    (comp (ref "R20")
      (value "R-EU_0617/17")
      (footprint "eagle-import:0617_17")
      (libsource (lib "eagle-import") (part "R-EU_0617/17"))
    )
    (comp (ref "R21")
      (value "R-EU_0617/17")
      (footprint "eagle-import:0617_17")
      (libsource (lib "eagle-import") (part "R-EU_0617/17"))
    )
    (comp (ref "R22")
      (value "R-EU_0617/17")
      (footprint "eagle-import:0617_17")
      (libsource (lib "eagle-import") (part "R-EU_0617/17"))
    )
    (comp (ref "R23")
      (value "R-EU_0617/17")
      (footprint "eagle-import:0617_17")
      (libsource (lib "eagle-import") (part "R-EU_0617/17"))
    )
    (comp (ref "R24")
      (value "R-EU_0617/17")
      (footprint "eagle-import:0617_17")
      (libsource (lib "eagle-import") (part "R-EU_0617/17"))
    )
    (comp (ref "R25")
      (value "R-EU_0617/17")
      (footprint "eagle-import:0617_17")
      (libsource (lib "eagle-import") (part "R-EU_0617/17"))
    )
    (comp (ref "R26")
      (value "R-EU_0617/17")
      (footprint "eagle-import:0617_17")
      (libsource (lib "eagle-import") (part "R-EU_0617/17"))
    )
    (comp (ref "R27")
      (value "R-EU_0617/17")
      (footprint "eagle-import:0617_17")
      (libsource (lib "eagle-import") (part "R-EU_0617/17"))
    )
    (comp (ref "R28")
      (value "R-EU_0617/17")
      (footprint "eagle-import:0617_17")
      (libsource (lib "eagle-import") (part "R-EU_0617/17"))
    )
    (comp (ref "R29")
      (value "R-EU_0617/17")
      (footprint "eagle-import:0617_17")
      (libsource (lib "eagle-import") (part "R-EU_0617/17"))
    )
    (comp (ref "R30")
      (value "R-EU_0617/17")
      (footprint "eagle-import:0617_17")
      (libsource (lib "eagle-import") (part "R-EU_0617/17"))
    )
    (comp (ref "R31")
      (value "R-EU_0617/17")
      (footprint "eagle-import:0617_17")
      (libsource (lib "eagle-import") (part "R-EU_0617/17"))
    )
    (comp (ref "R32")
      (value "R-EU_0617/17")
      (footprint "eagle-import:0617_17")
      (libsource (lib "eagle-import") (part "R-EU_0617/17"))
    )
    (comp (ref "R33")
      (value "R-EU_0617/17")
      (footprint "eagle-import:0617_17")
      (libsource (lib "eagle-import") (part "R-EU_0617/17"))
    )
    (comp (ref "R34")
      (value "R-EU_0617/17")
      (footprint "eagle-import:0617_17")
      (libsource (lib "eagle-import") (part "R-EU_0617/17"))
    )
    (comp (ref "R35")
      (value "R-EU_0617/17")
      (footprint "eagle-import:0617_17")
      (libsource (lib "eagle-import") (part "R-EU_0617/17"))
    )
    (comp (ref "R36")
      (value "R-EU_0617/17")
      (footprint "eagle-import:0617_17")
      (libsource (lib "eagle-import") (part "R-EU_0617/17"))
    )
    (comp (ref "R37")
      (value "R-EU_0617/17")
      (footprint "eagle-import:0617_17")
      (libsource (lib "eagle-import") (part "R-EU_0617/17"))
    )
    (comp (ref "R38")
      (value "R-EU_0617/17")
      (footprint "eagle-import:0617_17")
      (libsource (lib "eagle-import") (part "R-EU_0617/17"))
    )
    (comp (ref "R39")
      (value "R-EU_0617/17")
      (footprint "eagle-import:0617_17")
      (libsource (lib "eagle-import") (part "R-EU_0617/17"))
    )
    (comp (ref "R40")
      (value "R-EU_0617/17")
      (footprint "eagle-import:0617_17")
      (libsource (lib "eagle-import") (part "R-EU_0617/17"))
    )
    (comp (ref "R41")
      (value "R-EU_0617/17")
      (footprint "eagle-import:0617_17")
      (libsource (lib "eagle-import") (part "R-EU_0617/17"))
    )
    (comp (ref "R42")
      (value "R-EU_0617/17")
      (footprint "eagle-import:0617_17")
      (libsource (lib "eagle-import") (part "R-EU_0617/17"))
    )
    (comp (ref "R43")
      (value "R-EU_0617/17")
      (footprint "eagle-import:0617_17")
      (libsource (lib "eagle-import") (part "R-EU_0617/17"))
    )
    (comp (ref "R44")
      (value "R-EU_0617/17")
      (footprint "eagle-import:0617_17")
      (libsource (lib "eagle-import") (part "R-EU_0617/17"))
    )
    (comp (ref "R45")
      (value "R-EU_0617/17")
      (footprint "eagle-import:0617_17")
      (libsource (lib "eagle-import") (part "R-EU_0617/17"))
    )
    (comp (ref "R46")
      (value "R-EU_0617/17")
      (footprint "eagle-import:0617_17")
      (libsource (lib "eagle-import") (part "R-EU_0617/17"))
    )
    (comp (ref "R47")
      (value "R-EU_0617/17")
      (footprint "eagle-import:0617_17")
      (libsource (lib "eagle-import") (part "R-EU_0617/17"))
    )
    (comp (ref "R48")
      (value "R-EU_0617/17")
      (footprint "eagle-import:0617_17")
      (libsource (lib "eagle-import") (part "R-EU_0617/17"))
    )
    (comp (ref "R49")
      (value "R-EU_R0805")
      (footprint "eagle-import:R0805")
      (libsource (lib "eagle-import") (part "R-EU_R0805"))
    )
    (comp (ref "R50")
      (value "R-EU_R0805")
      (footprint "eagle-import:R0805")
      (libsource (lib "eagle-import") (part "R-EU_R0805"))
    )
    (comp (ref "R51")
      (value "R-EU_R0805")
      (footprint "eagle-import:R0805")
      (libsource (lib "eagle-import") (part "R-EU_R0805"))
    )
    (comp (ref "R52")
      (value "R-EU_R0805")
      (footprint "eagle-import:R0805")
      (libsource (lib "eagle-import") (part "R-EU_R0805"))
    )
    (comp (ref "R53")
      (value "R-EU_R0805")
      (footprint "eagle-import:R0805")
      (libsource (lib "eagle-import") (part "R-EU_R0805"))
    )
    (comp (ref "R54")
      (value "R-EU_R0805")
      (footprint "eagle-import:R0805")
      (libsource (lib "eagle-import") (part "R-EU_R0805"))
    )
    (comp (ref "R55")
      (value "R-EU_R0805")
      (footprint "eagle-import:R0805")
      (libsource (lib "eagle-import") (part "R-EU_R0805"))
    )
    (comp (ref "R56")
      (value "R-EU_R0805")
      (footprint "eagle-import:R0805")
      (libsource (lib "eagle-import") (part "R-EU_R0805"))
    )
    (comp (ref "R57")
      (value "R-EU_R0805")
      (footprint "eagle-import:R0805")
      (libsource (lib "eagle-import") (part "R-EU_R0805"))
    )
    (comp (ref "R58")
      (value "R-EU_R0805")
      (footprint "eagle-import:R0805")
      (libsource (lib "eagle-import") (part "R-EU_R0805"))
    )
    (comp (ref "R59")
      (value "R-EU_R0805")
      (footprint "eagle-import:R0805")
      (libsource (lib "eagle-import") (part "R-EU_R0805"))
    )
    (comp (ref "R60")
      (value "R-EU_R0805")
      (footprint "eagle-import:R0805")
      (libsource (lib "eagle-import") (part "R-EU_R0805"))
    )
    (comp (ref "R61")
      (value "R-EU_R0805")
      (footprint "eagle-import:R0805")
      (libsource (lib "eagle-import") (part "R-EU_R0805"))
    )
    (comp (ref "R62")
      (value "R-EU_R0805")
      (footprint "eagle-import:R0805")
      (libsource (lib "eagle-import") (part "R-EU_R0805"))
    )
    (comp (ref "R63")
      (value "R-EU_R0805")
      (footprint "eagle-import:R0805")
      (libsource (lib "eagle-import") (part "R-EU_R0805"))
    )
    (comp (ref "R64")
      (value "R-EU_R0805")
      (footprint "eagle-import:R0805")
      (libsource (lib "eagle-import") (part "R-EU_R0805"))
    )
    (comp (ref "R65")
      (value "R-EU_R0805")
      (footprint "eagle-import:R0805")
      (libsource (lib "eagle-import") (part "R-EU_R0805"))
    )
    (comp (ref "R66")
      (value "R-EU_R0805")
      (footprint "eagle-import:R0805")
      (libsource (lib "eagle-import") (part "R-EU_R0805"))
    )
    (comp (ref "R67")
      (value "R-EU_R0805")
      (footprint "eagle-import:R0805")
      (libsource (lib "eagle-import") (part "R-EU_R0805"))
    )
    (comp (ref "R68")
      (value "R-EU_R0805")
      (footprint "eagle-import:R0805")
      (libsource (lib "eagle-import") (part "R-EU_R0805"))
    )
    (comp (ref "R69")
      (value "R-EU_R0805")
      (footprint "eagle-import:R0805")
      (libsource (lib "eagle-import") (part "R-EU_R0805"))
    )
    (comp (ref "R70")
      (value "R-EU_R0805")
      (footprint "eagle-import:R0805")
      (libsource (lib "eagle-import") (part "R-EU_R0805"))
    )
    (comp (ref "R71")
      (value "R-EU_R0805")
      (footprint "eagle-import:R0805")
      (libsource (lib "eagle-import") (part "R-EU_R0805"))
    )
    (comp (ref "R72")
      (value "R-EU_R0805")
      (footprint "eagle-import:R0805")
      (libsource (lib "eagle-import") (part "R-EU_R0805"))
    )
    (comp (ref "R73")
      (value "R-EU_R0805")
      (footprint "eagle-import:R0805")
      (libsource (lib "eagle-import") (part "R-EU_R0805"))
    )
    (comp (ref "R74")
      (value "R-EU_R0805")
      (footprint "eagle-import:R0805")
      (libsource (lib "eagle-import") (part "R-EU_R0805"))
    )
    (comp (ref "R75")
      (value "R-EU_R0805")
      (footprint "eagle-import:R0805")
      (libsource (lib "eagle-import") (part "R-EU_R0805"))
    )
    (comp (ref "R76")
      (value "R-EU_R0805")
      (footprint "eagle-import:R0805")
      (libsource (lib "eagle-import") (part "R-EU_R0805"))
    )
    (comp (ref "R77")
      (value "R-EU_R0805")
      (footprint "eagle-import:R0805")
      (libsource (lib "eagle-import") (part "R-EU_R0805"))
    )
    (comp (ref "R78")
      (value "R-EU_R0805")
      (footprint "eagle-import:R0805")
      (libsource (lib "eagle-import") (part "R-EU_R0805"))
    )
    (comp (ref "R79")
      (value "R-EU_R0805")
      (footprint "eagle-import:R0805")
      (libsource (lib "eagle-import") (part "R-EU_R0805"))
    )
    (comp (ref "R80")
      (value "R-EU_R0805")
      (footprint "eagle-import:R0805")
      (libsource (lib "eagle-import") (part "R-EU_R0805"))
    )
    (comp (ref "R81")
      (value "R-EU_R0805")
      (footprint "eagle-import:R0805")
      (libsource (lib "eagle-import") (part "R-EU_R0805"))
    )
    (comp (ref "R82")
      (value "R-EU_R0805")
      (footprint "eagle-import:R0805")
      (libsource (lib "eagle-import") (part "R-EU_R0805"))
    )
    (comp (ref "R83")
      (value "R-EU_R0805")
      (footprint "eagle-import:R0805")
      (libsource (lib "eagle-import") (part "R-EU_R0805"))
    )
    (comp (ref "R84")
      (value "R-EU_R0805")
      (footprint "eagle-import:R0805")
      (libsource (lib "eagle-import") (part "R-EU_R0805"))
    )
    (comp (ref "R85")
      (value "R-EU_R0805")
      (footprint "eagle-import:R0805")
      (libsource (lib "eagle-import") (part "R-EU_R0805"))
    )
    (comp (ref "R86")
      (value "R-EU_R0805")
      (footprint "eagle-import:R0805")
      (libsource (lib "eagle-import") (part "R-EU_R0805"))
    )
    (comp (ref "R87")
      (value "R-EU_R0805")
      (footprint "eagle-import:R0805")
      (libsource (lib "eagle-import") (part "R-EU_R0805"))
    )
    (comp (ref "R88")
      (value "R-EU_R0805")
      (footprint "eagle-import:R0805")
      (libsource (lib "eagle-import") (part "R-EU_R0805"))
    )
    (comp (ref "R89")
      (value "R-EU_R0805")
      (footprint "eagle-import:R0805")
      (libsource (lib "eagle-import") (part "R-EU_R0805"))
    )
    (comp (ref "R90")
      (value "R-EU_R0805")
      (footprint "eagle-import:R0805")
      (libsource (lib "eagle-import") (part "R-EU_R0805"))
    )
    (comp (ref "R91")
      (value "R-EU_R0805")
      (footprint "eagle-import:R0805")
      (libsource (lib "eagle-import") (part "R-EU_R0805"))
    )
    (comp (ref "R92")
      (value "R-EU_R0805")
      (footprint "eagle-import:R0805")
      (libsource (lib "eagle-import") (part "R-EU_R0805"))
    )
    (comp (ref "R93")
      (value "R-EU_R0805")
      (footprint "eagle-import:R0805")
      (libsource (lib "eagle-import") (part "R-EU_R0805"))
    )
    (comp (ref "R94")
      (value "R-EU_R0805")
      (footprint "eagle-import:R0805")
      (libsource (lib "eagle-import") (part "R-EU_R0805"))
    )
    (comp (ref "R95")
      (value "R-EU_R0805")
      (footprint "eagle-import:R0805")
      (libsource (lib "eagle-import") (part "R-EU_R0805"))
    )
    (comp (ref "R96")
      (value "R-EU_R0805")
      (footprint "eagle-import:R0805")
      (libsource (lib "eagle-import") (part "R-EU_R0805"))
    )
    (comp (ref "R97")
      (value "R-EU_R0805")
      (footprint "eagle-import:R0805")
      (libsource (lib "eagle-import") (part "R-EU_R0805"))
    )
    (comp (ref "R98")
      (value "R-EU_R0805")
      (footprint "eagle-import:R0805")
      (libsource (lib "eagle-import") (part "R-EU_R0805"))
    )
    (comp (ref "R99")
      (value "R-EU_R0805")
      (footprint "eagle-import:R0805")
      (libsource (lib "eagle-import") (part "R-EU_R0805"))
    )
    (comp (ref "R100")
      (value "R-EU_R0805")
      (footprint "eagle-import:R0805")
      (libsource (lib "eagle-import") (part "R-EU_R0805"))
    )
    (comp (ref "R101")
      (value "R-EU_R0805")
      (footprint "eagle-import:R0805")
      (libsource (lib "eagle-import") (part "R-EU_R0805"))
    )
    (comp (ref "R102")
      (value "R-EU_R0805")
      (footprint "eagle-import:R0805")
      (libsource (lib "eagle-import") (part "R-EU_R0805"))
    )
    (comp (ref "R103")
      (value "R-EU_R0805")
      (footprint "eagle-import:R0805")
      (libsource (lib "eagle-import") (part "R-EU_R0805"))
    )
    (comp (ref "R104")
      (value "R-EU_R0805")
      (footprint "eagle-import:R0805")
      (libsource (lib "eagle-import") (part "R-EU_R0805"))
    )
    (comp (ref "R105")
      (value "R-EU_R0805")
      (footprint "eagle-import:R0805")
      (libsource (lib "eagle-import") (part "R-EU_R0805"))
    )
    (comp (ref "R106")
      (value "R-EU_R0805")
      (footprint "eagle-import:R0805")
      (libsource (lib "eagle-import") (part "R-EU_R0805"))
    )
    (comp (ref "R107")
      (value "R-EU_R0805")
      (footprint "eagle-import:R0805")
      (libsource (lib "eagle-import") (part "R-EU_R0805"))
    )
    (comp (ref "R108")
      (value "R-EU_R0805")
      (footprint "eagle-import:R0805")
      (libsource (lib "eagle-import") (part "R-EU_R0805"))
    )
    (comp (ref "R109")
      (value "R-EU_R0805")
      (footprint "eagle-import:R0805")
      (libsource (lib "eagle-import") (part "R-EU_R0805"))
    )
    (comp (ref "R110")
      (value "R-EU_R0805")
      (footprint "eagle-import:R0805")
      (libsource (lib "eagle-import") (part "R-EU_R0805"))
    )
    (comp (ref "R111")
      (value "R-EU_R0805")
      (footprint "eagle-import:R0805")
      (libsource (lib "eagle-import") (part "R-EU_R0805"))
    )
    (comp (ref "R112")
      (value "R-EU_R0805")
      (footprint "eagle-import:R0805")
      (libsource (lib "eagle-import") (part "R-EU_R0805"))
    )
    (comp (ref "R113")
      (value "R-EU_R0805")
      (footprint "eagle-import:R0805")
      (libsource (lib "eagle-import") (part "R-EU_R0805"))
    )
    (comp (ref "R114")
      (value "R-EU_R0805")
      (footprint "eagle-import:R0805")
      (libsource (lib "eagle-import") (part "R-EU_R0805"))
    )
    (comp (ref "R115")
      (value "R-EU_R0805")
      (footprint "eagle-import:R0805")
      (libsource (lib "eagle-import") (part "R-EU_R0805"))
    )
    (comp (ref "R116")
      (value "R-EU_R0805")
      (footprint "eagle-import:R0805")
      (libsource (lib "eagle-import") (part "R-EU_R0805"))
    )
    (comp (ref "S1")
      (value "31-XX")
      (footprint "eagle-import:B3F-31XX")
      (fields (field (name "MPN") "B3F-3100"))
      (libsource (lib "eagle-import") (part "31-XX"))
    )
    (comp (ref "SV1")
      (value "MA10-1")
      (footprint "eagle-import:MA10-1")
      (libsource (lib "eagle-import") (part "MA10-1"))
    )
    (comp (ref "TTL-RS1")
      (value "TTL-RS485")
      (footprint "eagle-import:TTL-RS485")
      (libsource (lib "eagle-import") (part "TTL-RS485"))
    )
    (comp (ref "U49")
      (value "PC817X2NIP0F")
      (footprint "eagle-import:SOT254P975X400-4N")
      (fields (field (name "MF") "Sharp Microelectronics"))
      (libsource (lib "eagle-import") (part "PC817X2NIP0F"))
    )
    (comp (ref "Z1")
      (value "DIODE-SOD123")
      (footprint "eagle-import:SOD123")
      (libsource (lib "eagle-import") (part "DIODE-SOD123"))
    )
    (comp (ref "Z2")
      (value "DIODE-SOD123")
      (footprint "eagle-import:SOD123")
      (libsource (lib "eagle-import") (part "DIODE-SOD123"))
    )
    (comp (ref "Z3")
      (value "DIODE-SOD123")
      (footprint "eagle-import:SOD123")
      (libsource (lib "eagle-import") (part "DIODE-SOD123"))
    )
    (comp (ref "Z4")
      (value "DIODE-SOD123")
      (footprint "eagle-import:SOD123")
      (libsource (lib "eagle-import") (part "DIODE-SOD123"))
    )
    (comp (ref "Z5")
      (value "DIODE-SOD123")
      (footprint "eagle-import:SOD123")
      (libsource (lib "eagle-import") (part "DIODE-SOD123"))
    )
    (comp (ref "Z6")
      (value "DIODE-SOD123")
      (footprint "eagle-import:SOD123")
      (libsource (lib "eagle-import") (part "DIODE-SOD123"))
    )
    (comp (ref "Z7")
      (value "DIODE-SOD123")
      (footprint "eagle-import:SOD123")
      (libsource (lib "eagle-import") (part "DIODE-SOD123"))
    )
    (comp (ref "Z8")
      (value "DIODE-SOD123")
      (footprint "eagle-import:SOD123")
      (libsource (lib "eagle-import") (part "DIODE-SOD123"))
    )
    (comp (ref "Z9")
      (value "DIODE-SOD123")
      (footprint "eagle-import:SOD123")
      (libsource (lib "eagle-import") (part "DIODE-SOD123"))
    )
    (comp (ref "Z10")
      (value "DIODE-SOD123")
      (footprint "eagle-import:SOD123")
      (libsource (lib "eagle-import") (part "DIODE-SOD123"))
    )
    (comp (ref "Z11")
      (value "DIODE-SOD123")
      (footprint "eagle-import:SOD123")
      (libsource (lib "eagle-import") (part "DIODE-SOD123"))
    )
    (comp (ref "Z12")
      (value "DIODE-SOD123")
      (footprint "eagle-import:SOD123")
      (libsource (lib "eagle-import") (part "DIODE-SOD123"))
    )
    (comp (ref "Z13")
      (value "DIODE-SOD123")
      (footprint "eagle-import:SOD123")
      (libsource (lib "eagle-import") (part "DIODE-SOD123"))
    )
    (comp (ref "Z14")
      (value "DIODE-SOD123")
      (footprint "eagle-import:SOD123")
      (libsource (lib "eagle-import") (part "DIODE-SOD123"))
    )
    (comp (ref "Z15")
      (value "DIODE-SOD123")
      (footprint "eagle-import:SOD123")
      (libsource (lib "eagle-import") (part "DIODE-SOD123"))
    )
    (comp (ref "Z16")
      (value "DIODE-SOD123")
      (footprint "eagle-import:SOD123")
      (libsource (lib "eagle-import") (part "DIODE-SOD123"))
    )
    (comp (ref "Z17")
      (value "DIODE-SOD123")
      (footprint "eagle-import:SOD123")
      (libsource (lib "eagle-import") (part "DIODE-SOD123"))
    )
    (comp (ref "Z18")
      (value "DIODE-SOD123")
      (footprint "eagle-import:SOD123")
      (libsource (lib "eagle-import") (part "DIODE-SOD123"))
    )
    (comp (ref "Z19")
      (value "DIODE-SOD123")
      (footprint "eagle-import:SOD123")
      (libsource (lib "eagle-import") (part "DIODE-SOD123"))
    )
    (comp (ref "Z20")
      (value "DIODE-SOD123")
      (footprint "eagle-import:SOD123")
      (libsource (lib "eagle-import") (part "DIODE-SOD123"))
    )
    (comp (ref "Z21")
      (value "DIODE-SOD123")
      (footprint "eagle-import:SOD123")
      (libsource (lib "eagle-import") (part "DIODE-SOD123"))
    )
    (comp (ref "Z22")
      (value "DIODE-SOD123")
      (footprint "eagle-import:SOD123")
      (libsource (lib "eagle-import") (part "DIODE-SOD123"))
    )
    (comp (ref "Z23")
      (value "DIODE-SOD123")
      (footprint "eagle-import:SOD123")
      (libsource (lib "eagle-import") (part "DIODE-SOD123"))
    )
    (comp (ref "Z24")
      (value "DIODE-SOD123")
      (footprint "eagle-import:SOD123")
      (libsource (lib "eagle-import") (part "DIODE-SOD123"))
    )
    (comp (ref "Z25")
      (value "DIODE-SOD123")
      (footprint "eagle-import:SOD123")
      (libsource (lib "eagle-import") (part "DIODE-SOD123"))
    )
    (comp (ref "Z26")
      (value "DIODE-SOD123")
      (footprint "eagle-import:SOD123")
      (libsource (lib "eagle-import") (part "DIODE-SOD123"))
    )
    (comp (ref "Z27")
      (value "DIODE-SOD123")
      (footprint "eagle-import:SOD123")
      (libsource (lib "eagle-import") (part "DIODE-SOD123"))
    )
    (comp (ref "Z28")
      (value "DIODE-SOD123")
      (footprint "eagle-import:SOD123")
      (libsource (lib "eagle-import") (part "DIODE-SOD123"))
    )
    (comp (ref "Z29")
      (value "DIODE-SOD123")
      (footprint "eagle-import:SOD123")
      (libsource (lib "eagle-import") (part "DIODE-SOD123"))
    )
    (comp (ref "Z30")
      (value "DIODE-SOD123")
      (footprint "eagle-import:SOD123")
      (libsource (lib "eagle-import") (part "DIODE-SOD123"))
    )
    (comp (ref "Z31")
      (value "DIODE-SOD123")
      (footprint "eagle-import:SOD123")
      (libsource (lib "eagle-import") (part "DIODE-SOD123"))
    )
    (comp (ref "Z32")
      (value "DIODE-SOD123")
      (footprint "eagle-import:SOD123")
      (libsource (lib "eagle-import") (part "DIODE-SOD123"))
    )
    (comp (ref "Z33")
      (value "DIODE-SOD123")
      (footprint "eagle-import:SOD123")
      (libsource (lib "eagle-import") (part "DIODE-SOD123"))
    )
    (comp (ref "Z34")
      (value "DIODE-SOD123")
      (footprint "eagle-import:SOD123")
      (libsource (lib "eagle-import") (part "DIODE-SOD123"))
    )
    (comp (ref "Z35")
      (value "DIODE-SOD123")
      (footprint "eagle-import:SOD123")
      (libsource (lib "eagle-import") (part "DIODE-SOD123"))
    )
    (comp (ref "Z36")
      (value "DIODE-SOD123")
      (footprint "eagle-import:SOD123")
      (libsource (lib "eagle-import") (part "DIODE-SOD123"))
    )
    (comp (ref "Z37")
      (value "DIODE-SOD123")
      (footprint "eagle-import:SOD123")
      (libsource (lib "eagle-import") (part "DIODE-SOD123"))
    )
    (comp (ref "Z38")
      (value "DIODE-SOD123")
      (footprint "eagle-import:SOD123")
      (libsource (lib "eagle-import") (part "DIODE-SOD123"))
    )
    (comp (ref "Z39")
      (value "DIODE-SOD123")
      (footprint "eagle-import:SOD123")
      (libsource (lib "eagle-import") (part "DIODE-SOD123"))
    )
    (comp (ref "Z40")
      (value "DIODE-SOD123")
      (footprint "eagle-import:SOD123")
      (libsource (lib "eagle-import") (part "DIODE-SOD123"))
    )
    (comp (ref "Z41")
      (value "DIODE-SOD123")
      (footprint "eagle-import:SOD123")
      (libsource (lib "eagle-import") (part "DIODE-SOD123"))
    )
    (comp (ref "Z42")
      (value "DIODE-SOD123")
      (footprint "eagle-import:SOD123")
      (libsource (lib "eagle-import") (part "DIODE-SOD123"))
    )
    (comp (ref "Z43")
      (value "DIODE-SOD123")
      (footprint "eagle-import:SOD123")
      (libsource (lib "eagle-import") (part "DIODE-SOD123"))
    )
    (comp (ref "Z44")
      (value "DIODE-SOD123")
      (footprint "eagle-import:SOD123")
      (libsource (lib "eagle-import") (part "DIODE-SOD123"))
    )
    (comp (ref "Z45")
      (value "DIODE-SOD123")
      (footprint "eagle-import:SOD123")
      (libsource (lib "eagle-import") (part "DIODE-SOD123"))
    )
    (comp (ref "Z46")
      (value "DIODE-SOD123")
      (footprint "eagle-import:SOD123")
      (libsource (lib "eagle-import") (part "DIODE-SOD123"))
    )
    (comp (ref "Z47")
      (value "DIODE-SOD123")
      (footprint "eagle-import:SOD123")
      (libsource (lib "eagle-import") (part "DIODE-SOD123"))
    )
    (comp (ref "Z48")
      (value "DIODE-SOD123")
      (footprint "eagle-import:SOD123")
      (libsource (lib "eagle-import") (part "DIODE-SOD123"))
    )
  )
  (nets
    (net (code "1") (name "/A+") (class "Default")
      (node (ref "SV1") (pin "5") (pinfunction "5_5") (pintype "passive"))
      (node (ref "TTL-RS1") (pin "A") (pinfunction "A_A") (pintype "bidirectional"))
    )
    (net (code "2") (name "/B-") (class "Default")
      (node (ref "SV1") (pin "6") (pinfunction "6_6") (pintype "passive"))
      (node (ref "TTL-RS1") (pin "B") (pinfunction "B_B") (pintype "bidirectional"))
    )
    (net (code "3") (name "/COMM") (class "Default")
      (node (ref "HEADER-22P1") (pin "20") (pinfunction "20_20") (pintype "bidirectional"))
      (node (ref "OPTO1") (pin "2") (pinfunction "C_2") (pintype "passive"))
      (node (ref "OPTO10") (pin "2") (pinfunction "C_2") (pintype "passive"))
      (node (ref "OPTO11") (pin "2") (pinfunction "C_2") (pintype "passive"))
      (node (ref "OPTO12") (pin "2") (pinfunction "C_2") (pintype "passive"))
      (node (ref "OPTO13") (pin "2") (pinfunction "C_2") (pintype "passive"))
      (node (ref "OPTO14") (pin "2") (pinfunction "C_2") (pintype "passive"))
      (node (ref "OPTO15") (pin "2") (pinfunction "C_2") (pintype "passive"))
      (node (ref "OPTO16") (pin "2") (pinfunction "C_2") (pintype "passive"))
      (node (ref "OPTO17") (pin "2") (pinfunction "C_2") (pintype "passive"))
      (node (ref "OPTO18") (pin "2") (pinfunction "C_2") (pintype "passive"))
      (node (ref "OPTO19") (pin "2") (pinfunction "C_2") (pintype "passive"))
      (node (ref "OPTO2") (pin "2") (pinfunction "C_2") (pintype "passive"))
      (node (ref "OPTO20") (pin "2") (pinfunction "C_2") (pintype "passive"))
      (node (ref "OPTO21") (pin "2") (pinfunction "C_2") (pintype "passive"))
      (node (ref "OPTO22") (pin "2") (pinfunction "C_2") (pintype "passive"))
      (node (ref "OPTO23") (pin "2") (pinfunction "C_2") (pintype "passive"))
      (node (ref "OPTO24") (pin "2") (pinfunction "C_2") (pintype "passive"))
      (node (ref "OPTO25") (pin "2") (pinfunction "C_2") (pintype "passive"))
      (node (ref "OPTO26") (pin "2") (pinfunction "C_2") (pintype "passive"))
      (node (ref "OPTO27") (pin "2") (pinfunction "C_2") (pintype "passive"))
      (node (ref "OPTO28") (pin "2") (pinfunction "C_2") (pintype "passive"))
      (node (ref "OPTO29") (pin "2") (pinfunction "C_2") (pintype "passive"))
      (node (ref "OPTO3") (pin "2") (pinfunction "C_2") (pintype "passive"))
      (node (ref "OPTO30") (pin "2") (pinfunction "C_2") (pintype "passive"))
      (node (ref "OPTO31") (pin "2") (pinfunction "C_2") (pintype "passive"))
      (node (ref "OPTO32") (pin "2") (pinfunction "C_2") (pintype "passive"))
      (node (ref "OPTO33") (pin "2") (pinfunction "C_2") (pintype "passive"))
      (node (ref "OPTO34") (pin "2") (pinfunction "C_2") (pintype "passive"))
      (node (ref "OPTO35") (pin "2") (pinfunction "C_2") (pintype "passive"))
      (node (ref "OPTO36") (pin "2") (pinfunction "C_2") (pintype "passive"))
      (node (ref "OPTO37") (pin "2") (pinfunction "C_2") (pintype "passive"))
      (node (ref "OPTO38") (pin "2") (pinfunction "C_2") (pintype "passive"))
      (node (ref "OPTO39") (pin "2") (pinfunction "C_2") (pintype "passive"))
      (node (ref "OPTO4") (pin "2") (pinfunction "C_2") (pintype "passive"))
      (node (ref "OPTO40") (pin "2") (pinfunction "C_2") (pintype "passive"))
      (node (ref "OPTO41") (pin "2") (pinfunction "C_2") (pintype "passive"))
      (node (ref "OPTO42") (pin "2") (pinfunction "C_2") (pintype "passive"))
      (node (ref "OPTO43") (pin "2") (pinfunction "C_2") (pintype "passive"))
      (node (ref "OPTO44") (pin "2") (pinfunction "C_2") (pintype "passive"))
      (node (ref "OPTO45") (pin "2") (pinfunction "C_2") (pintype "passive"))
      (node (ref "OPTO46") (pin "2") (pinfunction "C_2") (pintype "passive"))
      (node (ref "OPTO47") (pin "2") (pinfunction "C_2") (pintype "passive"))
      (node (ref "OPTO48") (pin "2") (pinfunction "C_2") (pintype "passive"))
      (node (ref "OPTO5") (pin "2") (pinfunction "C_2") (pintype "passive"))
      (node (ref "OPTO6") (pin "2") (pinfunction "C_2") (pintype "passive"))
      (node (ref "OPTO7") (pin "2") (pinfunction "C_2") (pintype "passive"))
      (node (ref "OPTO8") (pin "2") (pinfunction "C_2") (pintype "passive"))
      (node (ref "OPTO9") (pin "2") (pinfunction "C_2") (pintype "passive"))
      (node (ref "Z1") (pin "A") (pinfunction "A_A") (pintype "passive"))
      (node (ref "Z10") (pin "A") (pinfunction "A_A") (pintype "passive"))
      (node (ref "Z11") (pin "A") (pinfunction "A_A") (pintype "passive"))
      (node (ref "Z12") (pin "A") (pinfunction "A_A") (pintype "passive"))
      (node (ref "Z13") (pin "A") (pinfunction "A_A") (pintype "passive"))
      (node (ref "Z14") (pin "A") (pinfunction "A_A") (pintype "passive"))
      (node (ref "Z15") (pin "A") (pinfunction "A_A") (pintype "passive"))
      (node (ref "Z16") (pin "A") (pinfunction "A_A") (pintype "passive"))
      (node (ref "Z17") (pin "A") (pinfunction "A_A") (pintype "passive"))
      (node (ref "Z18") (pin "A") (pinfunction "A_A") (pintype "passive"))
      (node (ref "Z19") (pin "A") (pinfunction "A_A") (pintype "passive"))
      (node (ref "Z2") (pin "A") (pinfunction "A_A") (pintype "passive"))
      (node (ref "Z20") (pin "A") (pinfunction "A_A") (pintype "passive"))
      (node (ref "Z21") (pin "A") (pinfunction "A_A") (pintype "passive"))
      (node (ref "Z22") (pin "A") (pinfunction "A_A") (pintype "passive"))
      (node (ref "Z23") (pin "A") (pinfunction "A_A") (pintype "passive"))
      (node (ref "Z24") (pin "A") (pinfunction "A_A") (pintype "passive"))
      (node (ref "Z25") (pin "A") (pinfunction "A_A") (pintype "passive"))
      (node (ref "Z26") (pin "A") (pinfunction "A_A") (pintype "passive"))
      (node (ref "Z27") (pin "A") (pinfunction "A_A") (pintype "passive"))
      (node (ref "Z28") (pin "A") (pinfunction "A_A") (pintype "passive"))
      (node (ref "Z29") (pin "A") (pinfunction "A_A") (pintype "passive"))
      (node (ref "Z3") (pin "A") (pinfunction "A_A") (pintype "passive"))
      (node (ref "Z30") (pin "A") (pinfunction "A_A") (pintype "passive"))
      (node (ref "Z31") (pin "A") (pinfunction "A_A") (pintype "passive"))
      (node (ref "Z32") (pin "A") (pinfunction "A_A") (pintype "passive"))
      (node (ref "Z33") (pin "A") (pinfunction "A_A") (pintype "passive"))
      (node (ref "Z34") (pin "A") (pinfunction "A_A") (pintype "passive"))
      (node (ref "Z35") (pin "A") (pinfunction "A_A") (pintype "passive"))
      (node (ref "Z36") (pin "A") (pinfunction "A_A") (pintype "passive"))
      (node (ref "Z37") (pin "A") (pinfunction "A_A") (pintype "passive"))
      (node (ref "Z38") (pin "A") (pinfunction "A_A") (pintype "passive"))
      (node (ref "Z39") (pin "A") (pinfunction "A_A") (pintype "passive"))
      (node (ref "Z4") (pin "A") (pinfunction "A_A") (pintype "passive"))
      (node (ref "Z40") (pin "A") (pinfunction "A_A") (pintype "passive"))
      (node (ref "Z41") (pin "A") (pinfunction "A_A") (pintype "passive"))
      (node (ref "Z42") (pin "A") (pinfunction "A_A") (pintype "passive"))
      (node (ref "Z43") (pin "A") (pinfunction "A_A") (pintype "passive"))
      (node (ref "Z44") (pin "A") (pinfunction "A_A") (pintype "passive"))
      (node (ref "Z45") (pin "A") (pinfunction "A_A") (pintype "passive"))
      (node (ref "Z46") (pin "A") (pinfunction "A_A") (pintype "passive"))
      (node (ref "Z47") (pin "A") (pinfunction "A_A") (pintype "passive"))
      (node (ref "Z48") (pin "A") (pinfunction "A_A") (pintype "passive"))
      (node (ref "Z5") (pin "A") (pinfunction "A_A") (pintype "passive"))
      (node (ref "Z6") (pin "A") (pinfunction "A_A") (pintype "passive"))
      (node (ref "Z7") (pin "A") (pinfunction "A_A") (pintype "passive"))
      (node (ref "Z8") (pin "A") (pinfunction "A_A") (pintype "passive"))
      (node (ref "Z9") (pin "A") (pinfunction "A_A") (pintype "passive"))
    )
    (net (code "4") (name "/COMMON") (class "Default")
      (node (ref "J2") (pin "2") (pinfunction "2_2") (pintype "passive"))
      (node (ref "K1") (pin "COM") (pinfunction "COM_COM") (pintype "passive"))
    )
    (net (code "5") (name "/NC") (class "Default")
      (node (ref "J2") (pin "1") (pinfunction "1_1") (pintype "passive"))
      (node (ref "K1") (pin "NC") (pinfunction "NC_NC") (pintype "passive"))
    )
    (net (code "6") (name "/NO") (class "Default")
      (node (ref "J2") (pin "3") (pinfunction "3_3") (pintype "passive"))
      (node (ref "K1") (pin "NO") (pinfunction "NO_NO") (pintype "passive"))
    )
    (net (code "7") (name "/OUT1") (class "Default")
      (node (ref "IC4") (pin "21") (pinfunction "GPA0_21") (pintype "bidirectional"))
      (node (ref "OPTO1") (pin "4") (pinfunction "CT_4") (pintype "passive"))
      (node (ref "R49") (pin "1") (pinfunction "1_1") (pintype "passive"))
    )
    (net (code "8") (name "/OUT2") (class "Default")
      (node (ref "IC4") (pin "22") (pinfunction "GPA1_22") (pintype "bidirectional"))
      (node (ref "OPTO2") (pin "4") (pinfunction "CT_4") (pintype "passive"))
      (node (ref "R50") (pin "1") (pinfunction "1_1") (pintype "passive"))
    )
    (net (code "9") (name "/OUT3") (class "Default")
      (node (ref "IC4") (pin "23") (pinfunction "GPA2_23") (pintype "bidirectional"))
      (node (ref "OPTO3") (pin "4") (pinfunction "CT_4") (pintype "passive"))
      (node (ref "R51") (pin "1") (pinfunction "1_1") (pintype "passive"))
    )
    (net (code "10") (name "/OUT4") (class "Default")
      (node (ref "IC4") (pin "24") (pinfunction "GPA3_24") (pintype "bidirectional"))
      (node (ref "OPTO4") (pin "4") (pinfunction "CT_4") (pintype "passive"))
      (node (ref "R52") (pin "1") (pinfunction "1_1") (pintype "passive"))
    )
    (net (code "11") (name "/OUT5") (class "Default")
      (node (ref "IC4") (pin "25") (pinfunction "GPA4_25") (pintype "bidirectional"))
      (node (ref "OPTO5") (pin "4") (pinfunction "CT_4") (pintype "passive"))
      (node (ref "R53") (pin "1") (pinfunction "1_1") (pintype "passive"))
    )
    (net (code "12") (name "/OUT6") (class "Default")
      (node (ref "IC4") (pin "26") (pinfunction "GPA5_26") (pintype "bidirectional"))
      (node (ref "OPTO6") (pin "4") (pinfunction "CT_4") (pintype "passive"))
      (node (ref "R54") (pin "1") (pinfunction "1_1") (pintype "passive"))
    )
    (net (code "13") (name "/OUT7") (class "Default")
      (node (ref "IC4") (pin "27") (pinfunction "GPA6_27") (pintype "bidirectional"))
      (node (ref "OPTO7") (pin "4") (pinfunction "CT_4") (pintype "passive"))
      (node (ref "R55") (pin "1") (pinfunction "1_1") (pintype "passive"))
    )
    (net (code "14") (name "/OUT8") (class "Default")
      (node (ref "IC4") (pin "28") (pinfunction "GPA7_28") (pintype "bidirectional"))
      (node (ref "OPTO8") (pin "4") (pinfunction "CT_4") (pintype "passive"))
      (node (ref "R56") (pin "1") (pinfunction "1_1") (pintype "passive"))
    )
    (net (code "15") (name "/OUT9") (class "Default")
      (node (ref "IC4") (pin "1") (pinfunction "GPB0_1") (pintype "bidirectional"))
      (node (ref "OPTO9") (pin "4") (pinfunction "CT_4") (pintype "passive"))
      (node (ref "R57") (pin "1") (pinfunction "1_1") (pintype "passive"))
    )
    (net (code "16") (name "/OUT10") (class "Default")
      (node (ref "IC4") (pin "2") (pinfunction "GPB1_2") (pintype "bidirectional"))
      (node (ref "OPTO10") (pin "4") (pinfunction "CT_4") (pintype "passive"))
      (node (ref "R58") (pin "1") (pinfunction "1_1") (pintype "passive"))
    )
    (net (code "17") (name "/OUT11") (class "Default")
      (node (ref "IC4") (pin "3") (pinfunction "GPB2_3") (pintype "bidirectional"))
      (node (ref "OPTO11") (pin "4") (pinfunction "CT_4") (pintype "passive"))
      (node (ref "R59") (pin "1") (pinfunction "1_1") (pintype "passive"))
    )
    (net (code "18") (name "/OUT12") (class "Default")
      (node (ref "IC4") (pin "4") (pinfunction "GPB3_4") (pintype "bidirectional"))
      (node (ref "OPTO12") (pin "4") (pinfunction "CT_4") (pintype "passive"))
      (node (ref "R60") (pin "1") (pinfunction "1_1") (pintype "passive"))
    )
    (net (code "19") (name "/OUT13") (class "Default")
      (node (ref "IC4") (pin "5") (pinfunction "GPB4_5") (pintype "bidirectional"))
      (node (ref "OPTO13") (pin "4") (pinfunction "CT_4") (pintype "passive"))
      (node (ref "R61") (pin "1") (pinfunction "1_1") (pintype "passive"))
    )
    (net (code "20") (name "/OUT14") (class "Default")
      (node (ref "IC4") (pin "6") (pinfunction "GPB5_6") (pintype "bidirectional"))
      (node (ref "OPTO14") (pin "4") (pinfunction "CT_4") (pintype "passive"))
      (node (ref "R62") (pin "1") (pinfunction "1_1") (pintype "passive"))
    )
    (net (code "21") (name "/OUT15") (class "Default")
      (node (ref "IC4") (pin "7") (pinfunction "GPB6_7") (pintype "bidirectional"))
      (node (ref "OPTO15") (pin "4") (pinfunction "CT_4") (pintype "passive"))
      (node (ref "R63") (pin "1") (pinfunction "1_1") (pintype "passive"))
    )
    (net (code "22") (name "/OUT16") (class "Default")
      (node (ref "IC4") (pin "8") (pinfunction "GPB7_8") (pintype "bidirectional"))
      (node (ref "OPTO16") (pin "4") (pinfunction "CT_4") (pintype "passive"))
      (node (ref "R64") (pin "1") (pinfunction "1_1") (pintype "passive"))
    )
    (net (code "23") (name "/OUT17") (class "Default")
      (node (ref "IC1") (pin "21") (pinfunction "GPA0_21") (pintype "bidirectional"))
      (node (ref "OPTO17") (pin "4") (pinfunction "CT_4") (pintype "passive"))
      (node (ref "R65") (pin "1") (pinfunction "1_1") (pintype "passive"))
    )
    (net (code "24") (name "/OUT18") (class "Default")
      (node (ref "IC1") (pin "22") (pinfunction "GPA1_22") (pintype "bidirectional"))
      (node (ref "OPTO18") (pin "4") (pinfunction "CT_4") (pintype "passive"))
      (node (ref "R66") (pin "1") (pinfunction "1_1") (pintype "passive"))
    )
    (net (code "25") (name "/OUT19") (class "Default")
      (node (ref "IC1") (pin "23") (pinfunction "GPA2_23") (pintype "bidirectional"))
      (node (ref "OPTO19") (pin "4") (pinfunction "CT_4") (pintype "passive"))
      (node (ref "R67") (pin "1") (pinfunction "1_1") (pintype "passive"))
    )
    (net (code "26") (name "/OUT20") (class "Default")
      (node (ref "IC1") (pin "24") (pinfunction "GPA3_24") (pintype "bidirectional"))
      (node (ref "OPTO20") (pin "4") (pinfunction "CT_4") (pintype "passive"))
      (node (ref "R68") (pin "1") (pinfunction "1_1") (pintype "passive"))
    )
    (net (code "27") (name "/OUT21") (class "Default")
      (node (ref "IC1") (pin "25") (pinfunction "GPA4_25") (pintype "bidirectional"))
      (node (ref "OPTO21") (pin "4") (pinfunction "CT_4") (pintype "passive"))
      (node (ref "R69") (pin "1") (pinfunction "1_1") (pintype "passive"))
    )
    (net (code "28") (name "/OUT22") (class "Default")
      (node (ref "IC1") (pin "26") (pinfunction "GPA5_26") (pintype "bidirectional"))
      (node (ref "OPTO22") (pin "4") (pinfunction "CT_4") (pintype "passive"))
      (node (ref "R70") (pin "1") (pinfunction "1_1") (pintype "passive"))
    )
    (net (code "29") (name "/OUT23") (class "Default")
      (node (ref "IC1") (pin "27") (pinfunction "GPA6_27") (pintype "bidirectional"))
      (node (ref "OPTO23") (pin "4") (pinfunction "CT_4") (pintype "passive"))
      (node (ref "R71") (pin "1") (pinfunction "1_1") (pintype "passive"))
    )
    (net (code "30") (name "/OUT24") (class "Default")
      (node (ref "IC1") (pin "28") (pinfunction "GPA7_28") (pintype "bidirectional"))
      (node (ref "OPTO24") (pin "4") (pinfunction "CT_4") (pintype "passive"))
      (node (ref "R72") (pin "1") (pinfunction "1_1") (pintype "passive"))
    )
    (net (code "31") (name "/OUT25") (class "Default")
      (node (ref "IC1") (pin "1") (pinfunction "GPB0_1") (pintype "bidirectional"))
      (node (ref "OPTO25") (pin "4") (pinfunction "CT_4") (pintype "passive"))
      (node (ref "R73") (pin "1") (pinfunction "1_1") (pintype "passive"))
    )
    (net (code "32") (name "/OUT26") (class "Default")
      (node (ref "IC1") (pin "2") (pinfunction "GPB1_2") (pintype "bidirectional"))
      (node (ref "OPTO26") (pin "4") (pinfunction "CT_4") (pintype "passive"))
      (node (ref "R74") (pin "1") (pinfunction "1_1") (pintype "passive"))
    )
    (net (code "33") (name "/OUT27") (class "Default")
      (node (ref "IC1") (pin "3") (pinfunction "GPB2_3") (pintype "bidirectional"))
      (node (ref "OPTO27") (pin "4") (pinfunction "CT_4") (pintype "passive"))
      (node (ref "R75") (pin "1") (pinfunction "1_1") (pintype "passive"))
    )
    (net (code "34") (name "/OUT28") (class "Default")
      (node (ref "IC1") (pin "4") (pinfunction "GPB3_4") (pintype "bidirectional"))
      (node (ref "OPTO28") (pin "4") (pinfunction "CT_4") (pintype "passive"))
      (node (ref "R76") (pin "1") (pinfunction "1_1") (pintype "passive"))
    )
    (net (code "35") (name "/OUT29") (class "Default")
      (node (ref "IC1") (pin "5") (pinfunction "GPB4_5") (pintype "bidirectional"))
      (node (ref "OPTO29") (pin "4") (pinfunction "CT_4") (pintype "passive"))
      (node (ref "R77") (pin "1") (pinfunction "1_1") (pintype "passive"))
    )
    (net (code "36") (name "/OUT30") (class "Default")
      (node (ref "IC1") (pin "6") (pinfunction "GPB5_6") (pintype "bidirectional"))
      (node (ref "OPTO30") (pin "4") (pinfunction "CT_4") (pintype "passive"))
      (node (ref "R78") (pin "1") (pinfunction "1_1") (pintype "passive"))
    )
    (net (code "37") (name "/OUT31") (class "Default")
      (node (ref "IC1") (pin "7") (pinfunction "GPB6_7") (pintype "bidirectional"))
      (node (ref "OPTO31") (pin "4") (pinfunction "CT_4") (pintype "passive"))
      (node (ref "R79") (pin "1") (pinfunction "1_1") (pintype "passive"))
    )
    (net (code "38") (name "/OUT32") (class "Default")
      (node (ref "IC1") (pin "8") (pinfunction "GPB7_8") (pintype "bidirectional"))
      (node (ref "OPTO32") (pin "4") (pinfunction "CT_4") (pintype "passive"))
      (node (ref "R80") (pin "1") (pinfunction "1_1") (pintype "passive"))
    )
    (net (code "39") (name "/OUT33") (class "Default")
      (node (ref "IC5") (pin "21") (pinfunction "GPA0_21") (pintype "bidirectional"))
      (node (ref "OPTO33") (pin "4") (pinfunction "CT_4") (pintype "passive"))
      (node (ref "R81") (pin "1") (pinfunction "1_1") (pintype "passive"))
    )
    (net (code "40") (name "/OUT34") (class "Default")
      (node (ref "IC5") (pin "22") (pinfunction "GPA1_22") (pintype "bidirectional"))
      (node (ref "OPTO34") (pin "4") (pinfunction "CT_4") (pintype "passive"))
      (node (ref "R82") (pin "1") (pinfunction "1_1") (pintype "passive"))
    )
    (net (code "41") (name "/OUT35") (class "Default")
      (node (ref "IC5") (pin "23") (pinfunction "GPA2_23") (pintype "bidirectional"))
      (node (ref "OPTO35") (pin "4") (pinfunction "CT_4") (pintype "passive"))
      (node (ref "R83") (pin "1") (pinfunction "1_1") (pintype "passive"))
    )
    (net (code "42") (name "/OUT36") (class "Default")
      (node (ref "IC5") (pin "24") (pinfunction "GPA3_24") (pintype "bidirectional"))
      (node (ref "OPTO36") (pin "4") (pinfunction "CT_4") (pintype "passive"))
      (node (ref "R84") (pin "1") (pinfunction "1_1") (pintype "passive"))
    )
    (net (code "43") (name "/OUT37") (class "Default")
      (node (ref "IC5") (pin "25") (pinfunction "GPA4_25") (pintype "bidirectional"))
      (node (ref "OPTO37") (pin "4") (pinfunction "CT_4") (pintype "passive"))
      (node (ref "R85") (pin "1") (pinfunction "1_1") (pintype "passive"))
    )
    (net (code "44") (name "/OUT38") (class "Default")
      (node (ref "IC5") (pin "26") (pinfunction "GPA5_26") (pintype "bidirectional"))
      (node (ref "OPTO38") (pin "4") (pinfunction "CT_4") (pintype "passive"))
      (node (ref "R86") (pin "1") (pinfunction "1_1") (pintype "passive"))
    )
    (net (code "45") (name "/OUT39") (class "Default")
      (node (ref "IC5") (pin "27") (pinfunction "GPA6_27") (pintype "bidirectional"))
      (node (ref "OPTO39") (pin "4") (pinfunction "CT_4") (pintype "passive"))
      (node (ref "R87") (pin "1") (pinfunction "1_1") (pintype "passive"))
    )
    (net (code "46") (name "/OUT40") (class "Default")
      (node (ref "IC5") (pin "28") (pinfunction "GPA7_28") (pintype "bidirectional"))
      (node (ref "OPTO40") (pin "4") (pinfunction "CT_4") (pintype "passive"))
      (node (ref "R88") (pin "1") (pinfunction "1_1") (pintype "passive"))
    )
    (net (code "47") (name "/OUT41") (class "Default")
      (node (ref "IC5") (pin "1") (pinfunction "GPB0_1") (pintype "bidirectional"))
      (node (ref "OPTO41") (pin "4") (pinfunction "CT_4") (pintype "passive"))
      (node (ref "R89") (pin "1") (pinfunction "1_1") (pintype "passive"))
    )
    (net (code "48") (name "/OUT42") (class "Default")
      (node (ref "IC5") (pin "2") (pinfunction "GPB1_2") (pintype "bidirectional"))
      (node (ref "OPTO42") (pin "4") (pinfunction "CT_4") (pintype "passive"))
      (node (ref "R90") (pin "1") (pinfunction "1_1") (pintype "passive"))
    )
    (net (code "49") (name "/OUT43") (class "Default")
      (node (ref "IC5") (pin "3") (pinfunction "GPB2_3") (pintype "bidirectional"))
      (node (ref "OPTO43") (pin "4") (pinfunction "CT_4") (pintype "passive"))
      (node (ref "R91") (pin "1") (pinfunction "1_1") (pintype "passive"))
    )
    (net (code "50") (name "/OUT44") (class "Default")
      (node (ref "IC5") (pin "4") (pinfunction "GPB3_4") (pintype "bidirectional"))
      (node (ref "OPTO44") (pin "4") (pinfunction "CT_4") (pintype "passive"))
      (node (ref "R92") (pin "1") (pinfunction "1_1") (pintype "passive"))
    )
    (net (code "51") (name "/OUT45") (class "Default")
      (node (ref "IC5") (pin "5") (pinfunction "GPB4_5") (pintype "bidirectional"))
      (node (ref "OPTO45") (pin "4") (pinfunction "CT_4") (pintype "passive"))
      (node (ref "R93") (pin "1") (pinfunction "1_1") (pintype "passive"))
    )
    (net (code "52") (name "/OUT46") (class "Default")
      (node (ref "IC5") (pin "6") (pinfunction "GPB5_6") (pintype "bidirectional"))
      (node (ref "OPTO46") (pin "4") (pinfunction "CT_4") (pintype "passive"))
      (node (ref "R94") (pin "1") (pinfunction "1_1") (pintype "passive"))
    )
    (net (code "53") (name "/OUT47") (class "Default")
      (node (ref "IC5") (pin "7") (pinfunction "GPB6_7") (pintype "bidirectional"))
      (node (ref "OPTO47") (pin "4") (pinfunction "CT_4") (pintype "passive"))
      (node (ref "R95") (pin "1") (pinfunction "1_1") (pintype "passive"))
    )
    (net (code "54") (name "/OUT48") (class "Default")
      (node (ref "IC5") (pin "8") (pinfunction "GPB7_8") (pintype "bidirectional"))
      (node (ref "OPTO48") (pin "4") (pinfunction "CT_4") (pintype "passive"))
      (node (ref "R96") (pin "1") (pinfunction "1_1") (pintype "passive"))
    )
    (net (code "55") (name "/P1") (class "Default")
      (node (ref "HEADER-29P1") (pin "1") (pinfunction "1_1") (pintype "bidirectional"))
      (node (ref "R1") (pin "1") (pinfunction "1_1") (pintype "passive"))
    )
    (net (code "56") (name "/P2") (class "Default")
      (node (ref "HEADER-29P1") (pin "2") (pinfunction "2_2") (pintype "bidirectional"))
      (node (ref "R2") (pin "1") (pinfunction "1_1") (pintype "passive"))
    )
    (net (code "57") (name "/P3") (class "Default")
      (node (ref "HEADER-29P1") (pin "3") (pinfunction "3_3") (pintype "bidirectional"))
      (node (ref "R3") (pin "1") (pinfunction "1_1") (pintype "passive"))
    )
    (net (code "58") (name "/P4") (class "Default")
      (node (ref "HEADER-29P1") (pin "4") (pinfunction "4_4") (pintype "bidirectional"))
      (node (ref "R4") (pin "1") (pinfunction "1_1") (pintype "passive"))
    )
    (net (code "59") (name "/P5") (class "Default")
      (node (ref "HEADER-29P1") (pin "5") (pinfunction "5_5") (pintype "bidirectional"))
      (node (ref "R5") (pin "1") (pinfunction "1_1") (pintype "passive"))
    )
    (net (code "60") (name "/P6") (class "Default")
      (node (ref "HEADER-29P1") (pin "6") (pinfunction "6_6") (pintype "bidirectional"))
      (node (ref "R6") (pin "1") (pinfunction "1_1") (pintype "passive"))
    )
    (net (code "61") (name "/P7") (class "Default")
      (node (ref "HEADER-29P1") (pin "7") (pinfunction "7_7") (pintype "bidirectional"))
      (node (ref "R7") (pin "1") (pinfunction "1_1") (pintype "passive"))
    )
    (net (code "62") (name "/P8") (class "Default")
      (node (ref "HEADER-29P1") (pin "8") (pinfunction "8_8") (pintype "bidirectional"))
      (node (ref "R8") (pin "1") (pinfunction "1_1") (pintype "passive"))
    )
    (net (code "63") (name "/P9") (class "Default")
      (node (ref "HEADER-29P1") (pin "9") (pinfunction "9_9") (pintype "bidirectional"))
      (node (ref "R9") (pin "1") (pinfunction "1_1") (pintype "passive"))
    )
    (net (code "64") (name "/P10") (class "Default")
      (node (ref "HEADER-29P1") (pin "10") (pinfunction "10_10") (pintype "bidirectional"))
      (node (ref "R10") (pin "1") (pinfunction "1_1") (pintype "passive"))
    )
    (net (code "65") (name "/P11") (class "Default")
      (node (ref "HEADER-29P1") (pin "11") (pinfunction "11_11") (pintype "bidirectional"))
      (node (ref "R11") (pin "1") (pinfunction "1_1") (pintype "passive"))
    )
    (net (code "66") (name "/P12") (class "Default")
      (node (ref "HEADER-29P1") (pin "12") (pinfunction "12_12") (pintype "bidirectional"))
      (node (ref "R12") (pin "1") (pinfunction "1_1") (pintype "passive"))
    )
    (net (code "67") (name "/P13") (class "Default")
      (node (ref "HEADER-29P1") (pin "13") (pinfunction "13_13") (pintype "bidirectional"))
      (node (ref "R13") (pin "1") (pinfunction "1_1") (pintype "passive"))
    )
    (net (code "68") (name "/P14") (class "Default")
      (node (ref "HEADER-29P1") (pin "14") (pinfunction "14_14") (pintype "bidirectional"))
      (node (ref "R14") (pin "1") (pinfunction "1_1") (pintype "passive"))
    )
    (net (code "69") (name "/P15") (class "Default")
      (node (ref "HEADER-29P1") (pin "15") (pinfunction "15_15") (pintype "bidirectional"))
      (node (ref "R15") (pin "1") (pinfunction "1_1") (pintype "passive"))
    )
    (net (code "70") (name "/P16") (class "Default")
      (node (ref "HEADER-29P1") (pin "16") (pinfunction "16_16") (pintype "bidirectional"))
      (node (ref "R16") (pin "1") (pinfunction "1_1") (pintype "passive"))
    )
    (net (code "71") (name "/P17") (class "Default")
      (node (ref "HEADER-29P1") (pin "17") (pinfunction "17_17") (pintype "bidirectional"))
      (node (ref "R17") (pin "1") (pinfunction "1_1") (pintype "passive"))
    )
    (net (code "72") (name "/P18") (class "Default")
      (node (ref "HEADER-29P1") (pin "18") (pinfunction "18_18") (pintype "bidirectional"))
      (node (ref "R18") (pin "1") (pinfunction "1_1") (pintype "passive"))
    )
    (net (code "73") (name "/P19") (class "Default")
      (node (ref "HEADER-29P1") (pin "19") (pinfunction "19_19") (pintype "bidirectional"))
      (node (ref "R19") (pin "1") (pinfunction "1_1") (pintype "passive"))
    )
    (net (code "74") (name "/P20") (class "Default")
      (node (ref "HEADER-29P1") (pin "20") (pinfunction "20_20") (pintype "bidirectional"))
      (node (ref "R20") (pin "1") (pinfunction "1_1") (pintype "passive"))
    )
    (net (code "75") (name "/P21") (class "Default")
      (node (ref "HEADER-29P1") (pin "21") (pinfunction "21_21") (pintype "bidirectional"))
      (node (ref "R21") (pin "1") (pinfunction "1_1") (pintype "passive"))
    )
    (net (code "76") (name "/P22") (class "Default")
      (node (ref "HEADER-29P1") (pin "22") (pinfunction "22_22") (pintype "bidirectional"))
      (node (ref "R22") (pin "1") (pinfunction "1_1") (pintype "passive"))
    )
    (net (code "77") (name "/P23") (class "Default")
      (node (ref "HEADER-29P1") (pin "23") (pinfunction "23_23") (pintype "bidirectional"))
      (node (ref "R23") (pin "1") (pinfunction "1_1") (pintype "passive"))
    )
    (net (code "78") (name "/P24") (class "Default")
      (node (ref "HEADER-29P1") (pin "24") (pinfunction "24_24") (pintype "bidirectional"))
      (node (ref "R24") (pin "1") (pinfunction "1_1") (pintype "passive"))
    )
    (net (code "79") (name "/P25") (class "Default")
      (node (ref "HEADER-29P1") (pin "25") (pinfunction "25_25") (pintype "bidirectional"))
      (node (ref "R25") (pin "1") (pinfunction "1_1") (pintype "passive"))
    )
    (net (code "80") (name "/P26") (class "Default")
      (node (ref "HEADER-29P1") (pin "26") (pinfunction "26_26") (pintype "bidirectional"))
      (node (ref "R26") (pin "1") (pinfunction "1_1") (pintype "passive"))
    )
    (net (code "81") (name "/P27") (class "Default")
      (node (ref "HEADER-29P1") (pin "27") (pinfunction "27_27") (pintype "bidirectional"))
      (node (ref "R27") (pin "1") (pinfunction "1_1") (pintype "passive"))
    )
    (net (code "82") (name "/P28") (class "Default")
      (node (ref "HEADER-29P1") (pin "28") (pinfunction "28_28") (pintype "bidirectional"))
      (node (ref "R28") (pin "1") (pinfunction "1_1") (pintype "passive"))
    )
    (net (code "83") (name "/P29") (class "Default")
      (node (ref "HEADER-29P1") (pin "29") (pinfunction "29_29") (pintype "bidirectional"))
      (node (ref "R29") (pin "1") (pinfunction "1_1") (pintype "passive"))
    )
    (net (code "84") (name "/P30") (class "Default")
      (node (ref "HEADER-22P1") (pin "1") (pinfunction "1_1") (pintype "bidirectional"))
      (node (ref "R30") (pin "1") (pinfunction "1_1") (pintype "passive"))
    )
    (net (code "85") (name "/P31") (class "Default")
      (node (ref "HEADER-22P1") (pin "2") (pinfunction "2_2") (pintype "bidirectional"))
      (node (ref "R31") (pin "1") (pinfunction "1_1") (pintype "passive"))
    )
    (net (code "86") (name "/P32") (class "Default")
      (node (ref "HEADER-22P1") (pin "3") (pinfunction "3_3") (pintype "bidirectional"))
      (node (ref "R32") (pin "1") (pinfunction "1_1") (pintype "passive"))
    )
    (net (code "87") (name "/P33") (class "Default")
      (node (ref "HEADER-22P1") (pin "4") (pinfunction "4_4") (pintype "bidirectional"))
      (node (ref "R33") (pin "1") (pinfunction "1_1") (pintype "passive"))
    )
    (net (code "88") (name "/P34") (class "Default")
      (node (ref "HEADER-22P1") (pin "5") (pinfunction "5_5") (pintype "bidirectional"))
      (node (ref "R34") (pin "1") (pinfunction "1_1") (pintype "passive"))
    )
    (net (code "89") (name "/P35") (class "Default")
      (node (ref "HEADER-22P1") (pin "6") (pinfunction "6_6") (pintype "bidirectional"))
      (node (ref "R35") (pin "1") (pinfunction "1_1") (pintype "passive"))
    )
    (net (code "90") (name "/P36") (class "Default")
      (node (ref "HEADER-22P1") (pin "7") (pinfunction "7_7") (pintype "bidirectional"))
      (node (ref "R36") (pin "1") (pinfunction "1_1") (pintype "passive"))
    )
    (net (code "91") (name "/P37") (class "Default")
      (node (ref "HEADER-22P1") (pin "8") (pinfunction "8_8") (pintype "bidirectional"))
      (node (ref "R37") (pin "1") (pinfunction "1_1") (pintype "passive"))
    )
    (net (code "92") (name "/P38") (class "Default")
      (node (ref "HEADER-22P1") (pin "9") (pinfunction "9_9") (pintype "bidirectional"))
      (node (ref "R38") (pin "1") (pinfunction "1_1") (pintype "passive"))
    )
    (net (code "93") (name "/P39") (class "Default")
      (node (ref "HEADER-22P1") (pin "10") (pinfunction "10_10") (pintype "bidirectional"))
      (node (ref "R39") (pin "1") (pinfunction "1_1") (pintype "passive"))
    )
    (net (code "94") (name "/P40") (class "Default")
      (node (ref "HEADER-22P1") (pin "11") (pinfunction "11_11") (pintype "bidirectional"))
      (node (ref "R40") (pin "1") (pinfunction "1_1") (pintype "passive"))
    )
    (net (code "95") (name "/P41") (class "Default")
      (node (ref "HEADER-22P1") (pin "12") (pinfunction "12_12") (pintype "bidirectional"))
      (node (ref "R41") (pin "1") (pinfunction "1_1") (pintype "passive"))
    )
    (net (code "96") (name "/P42") (class "Default")
      (node (ref "HEADER-22P1") (pin "13") (pinfunction "13_13") (pintype "bidirectional"))
      (node (ref "R42") (pin "1") (pinfunction "1_1") (pintype "passive"))
    )
    (net (code "97") (name "/P43") (class "Default")
      (node (ref "HEADER-22P1") (pin "14") (pinfunction "14_14") (pintype "bidirectional"))
      (node (ref "R43") (pin "1") (pinfunction "1_1") (pintype "passive"))
    )
    (net (code "98") (name "/P44") (class "Default")
      (node (ref "HEADER-22P1") (pin "15") (pinfunction "15_15") (pintype "bidirectional"))
      (node (ref "R44") (pin "1") (pinfunction "1_1") (pintype "passive"))
    )
    (net (code "99") (name "/P45") (class "Default")
      (node (ref "HEADER-22P1") (pin "16") (pinfunction "16_16") (pintype "bidirectional"))
      (node (ref "R45") (pin "1") (pinfunction "1_1") (pintype "passive"))
    )
    (net (code "100") (name "/P46") (class "Default")
      (node (ref "HEADER-22P1") (pin "17") (pinfunction "17_17") (pintype "bidirectional"))
      (node (ref "R46") (pin "1") (pinfunction "1_1") (pintype "passive"))
    )
    (net (code "101") (name "/P47") (class "Default")
      (node (ref "HEADER-22P1") (pin "18") (pinfunction "18_18") (pintype "bidirectional"))
      (node (ref "R47") (pin "1") (pinfunction "1_1") (pintype "passive"))
    )
    (net (code "102") (name "/P48") (class "Default")
      (node (ref "HEADER-22P1") (pin "19") (pinfunction "19_19") (pintype "bidirectional"))
      (node (ref "R48") (pin "1") (pinfunction "1_1") (pintype "passive"))
    )
    (net (code "103") (name "/RESET") (class "Default")
      (node (ref "IC1") (pin "18") (pinfunction "~{RESET}_18") (pintype "input"))
      (node (ref "IC4") (pin "18") (pinfunction "~{RESET}_18") (pintype "input"))
      (node (ref "IC5") (pin "18") (pinfunction "~{RESET}_18") (pintype "input"))
      (node (ref "R103") (pin "2") (pinfunction "2_2") (pintype "passive"))
      (node (ref "R107") (pin "1") (pinfunction "1_1") (pintype "passive"))
      (node (ref "R111") (pin "2") (pinfunction "2_2") (pintype "passive"))
      (node (ref "S1") (pin "2") (pinfunction "S_2") (pintype "passive"))
    )
    (net (code "104") (name "/RESET1") (class "Default")
      (node (ref "S1") (pin "1") (pinfunction "P_1") (pintype "passive"))
      (node (ref "SV1") (pin "4") (pinfunction "4_4") (pintype "passive"))
    )
    (net (code "105") (name "/RX") (class "Default")
      (node (ref "SV1") (pin "7") (pinfunction "7_7") (pintype "passive"))
      (node (ref "TTL-RS1") (pin "RX") (pinfunction "RX_RX") (pintype "bidirectional"))
    )
    (net (code "106") (name "/SCL") (class "Default")
      (node (ref "IC1") (pin "12") (pinfunction "SCL_12") (pintype "input"))
      (node (ref "IC4") (pin "12") (pinfunction "SCL_12") (pintype "input"))
      (node (ref "IC5") (pin "12") (pinfunction "SCL_12") (pintype "input"))
      (node (ref "R101") (pin "1") (pinfunction "1_1") (pintype "passive"))
      (node (ref "R97") (pin "1") (pinfunction "1_1") (pintype "passive"))
      (node (ref "R99") (pin "1") (pinfunction "1_1") (pintype "passive"))
      (node (ref "SV1") (pin "2") (pinfunction "2_2") (pintype "passive"))
    )
    (net (code "107") (name "/SDA") (class "Default")
      (node (ref "IC1") (pin "13") (pinfunction "SDA_13") (pintype "bidirectional"))
      (node (ref "IC4") (pin "13") (pinfunction "SDA_13") (pintype "bidirectional"))
      (node (ref "IC5") (pin "13") (pinfunction "SDA_13") (pintype "bidirectional"))
      (node (ref "R100") (pin "1") (pinfunction "1_1") (pintype "passive"))
      (node (ref "R102") (pin "1") (pinfunction "1_1") (pintype "passive"))
      (node (ref "R98") (pin "1") (pinfunction "1_1") (pintype "passive"))
      (node (ref "SV1") (pin "3") (pinfunction "3_3") (pintype "passive"))
    )
    (net (code "108") (name "/TX") (class "Default")
      (node (ref "SV1") (pin "8") (pinfunction "8_8") (pintype "passive"))
      (node (ref "TTL-RS1") (pin "TX") (pinfunction "TX_TX") (pintype "bidirectional"))
    )
    (net (code "109") (name "GND") (class "Default")
      (node (ref "IC1") (pin "10") (pinfunction "VSS_10") (pintype "power_in"))
      (node (ref "IC4") (pin "10") (pinfunction "VSS_10") (pintype "power_in"))
      (node (ref "IC5") (pin "10") (pinfunction "VSS_10") (pintype "power_in"))
      (node (ref "JP2") (pin "2") (pinfunction "2_2") (pintype "passive"))
      (node (ref "JP2") (pin "4") (pinfunction "4_4") (pintype "passive"))
      (node (ref "JP2") (pin "6") (pinfunction "6_6") (pintype "passive"))
      (node (ref "JP2") (pin "8") (pinfunction "8_8") (pintype "passive"))
      (node (ref "OPTO1") (pin "3") (pinfunction "ET_3") (pintype "passive"))
      (node (ref "OPTO10") (pin "3") (pinfunction "ET_3") (pintype "passive"))
      (node (ref "OPTO11") (pin "3") (pinfunction "ET_3") (pintype "passive"))
      (node (ref "OPTO12") (pin "3") (pinfunction "ET_3") (pintype "passive"))
      (node (ref "OPTO13") (pin "3") (pinfunction "ET_3") (pintype "passive"))
      (node (ref "OPTO14") (pin "3") (pinfunction "ET_3") (pintype "passive"))
      (node (ref "OPTO15") (pin "3") (pinfunction "ET_3") (pintype "passive"))
      (node (ref "OPTO16") (pin "3") (pinfunction "ET_3") (pintype "passive"))
      (node (ref "OPTO17") (pin "3") (pinfunction "ET_3") (pintype "passive"))
      (node (ref "OPTO18") (pin "3") (pinfunction "ET_3") (pintype "passive"))
      (node (ref "OPTO19") (pin "3") (pinfunction "ET_3") (pintype "passive"))
      (node (ref "OPTO2") (pin "3") (pinfunction "ET_3") (pintype "passive"))
      (node (ref "OPTO20") (pin "3") (pinfunction "ET_3") (pintype "passive"))
      (node (ref "OPTO21") (pin "3") (pinfunction "ET_3") (pintype "passive"))
      (node (ref "OPTO22") (pin "3") (pinfunction "ET_3") (pintype "passive"))
      (node (ref "OPTO23") (pin "3") (pinfunction "ET_3") (pintype "passive"))
      (node (ref "OPTO24") (pin "3") (pinfunction "ET_3") (pintype "passive"))
      (node (ref "OPTO25") (pin "3") (pinfunction "ET_3") (pintype "passive"))
      (node (ref "OPTO26") (pin "3") (pinfunction "ET_3") (pintype "passive"))
      (node (ref "OPTO27") (pin "3") (pinfunction "ET_3") (pintype "passive"))
      (node (ref "OPTO28") (pin "3") (pinfunction "ET_3") (pintype "passive"))
      (node (ref "OPTO29") (pin "3") (pinfunction "ET_3") (pintype "passive"))
      (node (ref "OPTO3") (pin "3") (pinfunction "ET_3") (pintype "passive"))
      (node (ref "OPTO30") (pin "3") (pinfunction "ET_3") (pintype "passive"))
      (node (ref "OPTO31") (pin "3") (pinfunction "ET_3") (pintype "passive"))
      (node (ref "OPTO32") (pin "3") (pinfunction "ET_3") (pintype "passive"))
      (node (ref "OPTO33") (pin "3") (pinfunction "ET_3") (pintype "passive"))
      (node (ref "OPTO34") (pin "3") (pinfunction "ET_3") (pintype "passive"))
      (node (ref "OPTO35") (pin "3") (pinfunction "ET_3") (pintype "passive"))
      (node (ref "OPTO36") (pin "3") (pinfunction "ET_3") (pintype "passive"))
      (node (ref "OPTO37") (pin "3") (pinfunction "ET_3") (pintype "passive"))
      (node (ref "OPTO38") (pin "3") (pinfunction "ET_3") (pintype "passive"))
      (node (ref "OPTO39") (pin "3") (pinfunction "ET_3") (pintype "passive"))
      (node (ref "OPTO4") (pin "3") (pinfunction "ET_3") (pintype "passive"))
      (node (ref "OPTO40") (pin "3") (pinfunction "ET_3") (pintype "passive"))
      (node (ref "OPTO41") (pin "3") (pinfunction "ET_3") (pintype "passive"))
      (node (ref "OPTO42") (pin "3") (pinfunction "ET_3") (pintype "passive"))
      (node (ref "OPTO43") (pin "3") (pinfunction "ET_3") (pintype "passive"))
      (node (ref "OPTO44") (pin "3") (pinfunction "ET_3") (pintype "passive"))
      (node (ref "OPTO45") (pin "3") (pinfunction "ET_3") (pintype "passive"))
      (node (ref "OPTO46") (pin "3") (pinfunction "ET_3") (pintype "passive"))
      (node (ref "OPTO47") (pin "3") (pinfunction "ET_3") (pintype "passive"))
      (node (ref "OPTO48") (pin "3") (pinfunction "ET_3") (pintype "passive"))
      (node (ref "OPTO5") (pin "3") (pinfunction "ET_3") (pintype "passive"))
      (node (ref "OPTO6") (pin "3") (pinfunction "ET_3") (pintype "passive"))
      (node (ref "OPTO7") (pin "3") (pinfunction "ET_3") (pintype "passive"))
      (node (ref "OPTO8") (pin "3") (pinfunction "ET_3") (pintype "passive"))
      (node (ref "OPTO9") (pin "3") (pinfunction "ET_3") (pintype "passive"))
      (node (ref "Q1") (pin "2") (pinfunction "E_2") (pintype "passive"))
      (node (ref "R104") (pin "1") (pinfunction "1_1") (pintype "passive"))
      (node (ref "R105") (pin "1") (pinfunction "1_1") (pintype "passive"))
      (node (ref "R106") (pin "1") (pinfunction "1_1") (pintype "passive"))
      (node (ref "R109") (pin "1") (pinfunction "1_1") (pintype "passive"))
      (node (ref "R110") (pin "1") (pinfunction "1_1") (pintype "passive"))
      (node (ref "R112") (pin "1") (pinfunction "1_1") (pintype "passive"))
      (node (ref "R114") (pin "1") (pinfunction "1_1") (pintype "passive"))
      (node (ref "SV1") (pin "10") (pinfunction "10_10") (pintype "passive"))
      (node (ref "TTL-RS1") (pin "GND") (pinfunction "GND_GND") (pintype "bidirectional"))
      (node (ref "U49") (pin "2") (pinfunction "C_2") (pintype "passive"))
    )
    (net (code "110") (name "Net-(D2-K)") (class "Default")
      (node (ref "D2") (pin "C") (pinfunction "K_C") (pintype "passive"))
      (node (ref "LED1") (pin "+") (pinfunction "+_+") (pintype "passive"))
    )
    (net (code "111") (name "Net-(D2-PadA)") (class "Default")
      (node (ref "D2") (pin "A") (pinfunction "A_A") (pintype "passive"))
      (node (ref "R1") (pin "2") (pinfunction "2_2") (pintype "passive"))
    )
    (net (code "112") (name "Net-(D3-K)") (class "Default")
      (node (ref "D3") (pin "C") (pinfunction "K_C") (pintype "passive"))
      (node (ref "LED2") (pin "+") (pinfunction "+_+") (pintype "passive"))
    )
    (net (code "113") (name "Net-(D3-PadA)") (class "Default")
      (node (ref "D3") (pin "A") (pinfunction "A_A") (pintype "passive"))
      (node (ref "R2") (pin "2") (pinfunction "2_2") (pintype "passive"))
    )
    (net (code "114") (name "Net-(D4-K)") (class "Default")
      (node (ref "D4") (pin "C") (pinfunction "K_C") (pintype "passive"))
      (node (ref "LED3") (pin "+") (pinfunction "+_+") (pintype "passive"))
    )
    (net (code "115") (name "Net-(D4-PadA)") (class "Default")
      (node (ref "D4") (pin "A") (pinfunction "A_A") (pintype "passive"))
      (node (ref "R3") (pin "2") (pinfunction "2_2") (pintype "passive"))
    )
    (net (code "116") (name "Net-(D5-K)") (class "Default")
      (node (ref "D5") (pin "C") (pinfunction "K_C") (pintype "passive"))
      (node (ref "LED4") (pin "+") (pinfunction "+_+") (pintype "passive"))
    )
    (net (code "117") (name "Net-(D5-PadA)") (class "Default")
      (node (ref "D5") (pin "A") (pinfunction "A_A") (pintype "passive"))
      (node (ref "R4") (pin "2") (pinfunction "2_2") (pintype "passive"))
    )
    (net (code "118") (name "Net-(D6-K)") (class "Default")
      (node (ref "D6") (pin "C") (pinfunction "K_C") (pintype "passive"))
      (node (ref "LED5") (pin "+") (pinfunction "+_+") (pintype "passive"))
    )
    (net (code "119") (name "Net-(D6-PadA)") (class "Default")
      (node (ref "D6") (pin "A") (pinfunction "A_A") (pintype "passive"))
      (node (ref "R5") (pin "2") (pinfunction "2_2") (pintype "passive"))
    )
    (net (code "120") (name "Net-(D7-K)") (class "Default")
      (node (ref "D7") (pin "C") (pinfunction "K_C") (pintype "passive"))
      (node (ref "LED6") (pin "+") (pinfunction "+_+") (pintype "passive"))
    )
    (net (code "121") (name "Net-(D7-PadA)") (class "Default")
      (node (ref "D7") (pin "A") (pinfunction "A_A") (pintype "passive"))
      (node (ref "R6") (pin "2") (pinfunction "2_2") (pintype "passive"))
    )
    (net (code "122") (name "Net-(D8-K)") (class "Default")
      (node (ref "D8") (pin "C") (pinfunction "K_C") (pintype "passive"))
      (node (ref "LED7") (pin "+") (pinfunction "+_+") (pintype "passive"))
    )
    (net (code "123") (name "Net-(D8-PadA)") (class "Default")
      (node (ref "D8") (pin "A") (pinfunction "A_A") (pintype "passive"))
      (node (ref "R7") (pin "2") (pinfunction "2_2") (pintype "passive"))
    )
    (net (code "124") (name "Net-(D9-K)") (class "Default")
      (node (ref "D9") (pin "C") (pinfunction "K_C") (pintype "passive"))
      (node (ref "LED8") (pin "+") (pinfunction "+_+") (pintype "passive"))
    )
    (net (code "125") (name "Net-(D9-PadA)") (class "Default")
      (node (ref "D9") (pin "A") (pinfunction "A_A") (pintype "passive"))
      (node (ref "R8") (pin "2") (pinfunction "2_2") (pintype "passive"))
    )
    (net (code "126") (name "Net-(D10-K)") (class "Default")
      (node (ref "D10") (pin "C") (pinfunction "K_C") (pintype "passive"))
      (node (ref "LED9") (pin "+") (pinfunction "+_+") (pintype "passive"))
    )
    (net (code "127") (name "Net-(D10-PadA)") (class "Default")
      (node (ref "D10") (pin "A") (pinfunction "A_A") (pintype "passive"))
      (node (ref "R9") (pin "2") (pinfunction "2_2") (pintype "passive"))
    )
    (net (code "128") (name "Net-(D11-K)") (class "Default")
      (node (ref "D11") (pin "C") (pinfunction "K_C") (pintype "passive"))
      (node (ref "LED10") (pin "+") (pinfunction "+_+") (pintype "passive"))
    )
    (net (code "129") (name "Net-(D11-PadA)") (class "Default")
      (node (ref "D11") (pin "A") (pinfunction "A_A") (pintype "passive"))
      (node (ref "R10") (pin "2") (pinfunction "2_2") (pintype "passive"))
    )
    (net (code "130") (name "Net-(D12-K)") (class "Default")
      (node (ref "D12") (pin "C") (pinfunction "K_C") (pintype "passive"))
      (node (ref "LED11") (pin "+") (pinfunction "+_+") (pintype "passive"))
    )
    (net (code "131") (name "Net-(D12-PadA)") (class "Default")
      (node (ref "D12") (pin "A") (pinfunction "A_A") (pintype "passive"))
      (node (ref "R11") (pin "2") (pinfunction "2_2") (pintype "passive"))
    )
    (net (code "132") (name "Net-(D13-K)") (class "Default")
      (node (ref "D13") (pin "C") (pinfunction "K_C") (pintype "passive"))
      (node (ref "LED12") (pin "+") (pinfunction "+_+") (pintype "passive"))
    )
    (net (code "133") (name "Net-(D13-PadA)") (class "Default")
      (node (ref "D13") (pin "A") (pinfunction "A_A") (pintype "passive"))
      (node (ref "R12") (pin "2") (pinfunction "2_2") (pintype "passive"))
    )
    (net (code "134") (name "Net-(D14-K)") (class "Default")
      (node (ref "D14") (pin "C") (pinfunction "K_C") (pintype "passive"))
      (node (ref "LED13") (pin "+") (pinfunction "+_+") (pintype "passive"))
    )
    (net (code "135") (name "Net-(D14-PadA)") (class "Default")
      (node (ref "D14") (pin "A") (pinfunction "A_A") (pintype "passive"))
      (node (ref "R13") (pin "2") (pinfunction "2_2") (pintype "passive"))
    )
    (net (code "136") (name "Net-(D15-K)") (class "Default")
      (node (ref "D15") (pin "C") (pinfunction "K_C") (pintype "passive"))
      (node (ref "LED14") (pin "+") (pinfunction "+_+") (pintype "passive"))
    )
    (net (code "137") (name "Net-(D15-PadA)") (class "Default")
      (node (ref "D15") (pin "A") (pinfunction "A_A") (pintype "passive"))
      (node (ref "R14") (pin "2") (pinfunction "2_2") (pintype "passive"))
    )
    (net (code "138") (name "Net-(D16-K)") (class "Default")
      (node (ref "D16") (pin "C") (pinfunction "K_C") (pintype "passive"))
      (node (ref "LED15") (pin "+") (pinfunction "+_+") (pintype "passive"))
    )
    (net (code "139") (name "Net-(D16-PadA)") (class "Default")
      (node (ref "D16") (pin "A") (pinfunction "A_A") (pintype "passive"))
      (node (ref "R15") (pin "2") (pinfunction "2_2") (pintype "passive"))
    )
    (net (code "140") (name "Net-(D17-K)") (class "Default")
      (node (ref "D17") (pin "C") (pinfunction "K_C") (pintype "passive"))
      (node (ref "LED16") (pin "+") (pinfunction "+_+") (pintype "passive"))
    )
    (net (code "141") (name "Net-(D17-PadA)") (class "Default")
      (node (ref "D17") (pin "A") (pinfunction "A_A") (pintype "passive"))
      (node (ref "R16") (pin "2") (pinfunction "2_2") (pintype "passive"))
    )
    (net (code "142") (name "Net-(D18-K)") (class "Default")
      (node (ref "D18") (pin "C") (pinfunction "K_C") (pintype "passive"))
      (node (ref "LED17") (pin "+") (pinfunction "+_+") (pintype "passive"))
    )
    (net (code "143") (name "Net-(D18-PadA)") (class "Default")
      (node (ref "D18") (pin "A") (pinfunction "A_A") (pintype "passive"))
      (node (ref "R17") (pin "2") (pinfunction "2_2") (pintype "passive"))
    )
    (net (code "144") (name "Net-(D19-K)") (class "Default")
      (node (ref "D19") (pin "C") (pinfunction "K_C") (pintype "passive"))
      (node (ref "LED18") (pin "+") (pinfunction "+_+") (pintype "passive"))
    )
    (net (code "145") (name "Net-(D19-PadA)") (class "Default")
      (node (ref "D19") (pin "A") (pinfunction "A_A") (pintype "passive"))
      (node (ref "R18") (pin "2") (pinfunction "2_2") (pintype "passive"))
    )
    (net (code "146") (name "Net-(D20-K)") (class "Default")
      (node (ref "D20") (pin "C") (pinfunction "K_C") (pintype "passive"))
      (node (ref "LED19") (pin "+") (pinfunction "+_+") (pintype "passive"))
    )
    (net (code "147") (name "Net-(D20-PadA)") (class "Default")
      (node (ref "D20") (pin "A") (pinfunction "A_A") (pintype "passive"))
      (node (ref "R19") (pin "2") (pinfunction "2_2") (pintype "passive"))
    )
    (net (code "148") (name "Net-(D21-K)") (class "Default")
      (node (ref "D21") (pin "C") (pinfunction "K_C") (pintype "passive"))
      (node (ref "LED20") (pin "+") (pinfunction "+_+") (pintype "passive"))
    )
    (net (code "149") (name "Net-(D21-PadA)") (class "Default")
      (node (ref "D21") (pin "A") (pinfunction "A_A") (pintype "passive"))
      (node (ref "R20") (pin "2") (pinfunction "2_2") (pintype "passive"))
    )
    (net (code "150") (name "Net-(D22-K)") (class "Default")
      (node (ref "D22") (pin "C") (pinfunction "K_C") (pintype "passive"))
      (node (ref "LED21") (pin "+") (pinfunction "+_+") (pintype "passive"))
    )
    (net (code "151") (name "Net-(D22-PadA)") (class "Default")
      (node (ref "D22") (pin "A") (pinfunction "A_A") (pintype "passive"))
      (node (ref "R21") (pin "2") (pinfunction "2_2") (pintype "passive"))
    )
    (net (code "152") (name "Net-(D23-K)") (class "Default")
      (node (ref "D23") (pin "C") (pinfunction "K_C") (pintype "passive"))
      (node (ref "LED22") (pin "+") (pinfunction "+_+") (pintype "passive"))
    )
    (net (code "153") (name "Net-(D23-PadA)") (class "Default")
      (node (ref "D23") (pin "A") (pinfunction "A_A") (pintype "passive"))
      (node (ref "R22") (pin "2") (pinfunction "2_2") (pintype "passive"))
    )
    (net (code "154") (name "Net-(D24-K)") (class "Default")
      (node (ref "D24") (pin "C") (pinfunction "K_C") (pintype "passive"))
      (node (ref "LED23") (pin "+") (pinfunction "+_+") (pintype "passive"))
    )
    (net (code "155") (name "Net-(D24-PadA)") (class "Default")
      (node (ref "D24") (pin "A") (pinfunction "A_A") (pintype "passive"))
      (node (ref "R23") (pin "2") (pinfunction "2_2") (pintype "passive"))
    )
    (net (code "156") (name "Net-(D25-K)") (class "Default")
      (node (ref "D25") (pin "C") (pinfunction "K_C") (pintype "passive"))
      (node (ref "LED24") (pin "+") (pinfunction "+_+") (pintype "passive"))
    )
    (net (code "157") (name "Net-(D25-PadA)") (class "Default")
      (node (ref "D25") (pin "A") (pinfunction "A_A") (pintype "passive"))
      (node (ref "R24") (pin "2") (pinfunction "2_2") (pintype "passive"))
    )
    (net (code "158") (name "Net-(D26-K)") (class "Default")
      (node (ref "D26") (pin "C") (pinfunction "K_C") (pintype "passive"))
      (node (ref "LED25") (pin "+") (pinfunction "+_+") (pintype "passive"))
    )
    (net (code "159") (name "Net-(D26-PadA)") (class "Default")
      (node (ref "D26") (pin "A") (pinfunction "A_A") (pintype "passive"))
      (node (ref "R25") (pin "2") (pinfunction "2_2") (pintype "passive"))
    )
    (net (code "160") (name "Net-(D27-K)") (class "Default")
      (node (ref "D27") (pin "C") (pinfunction "K_C") (pintype "passive"))
      (node (ref "LED26") (pin "+") (pinfunction "+_+") (pintype "passive"))
    )
    (net (code "161") (name "Net-(D27-PadA)") (class "Default")
      (node (ref "D27") (pin "A") (pinfunction "A_A") (pintype "passive"))
      (node (ref "R26") (pin "2") (pinfunction "2_2") (pintype "passive"))
    )
    (net (code "162") (name "Net-(D28-K)") (class "Default")
      (node (ref "D28") (pin "C") (pinfunction "K_C") (pintype "passive"))
      (node (ref "LED27") (pin "+") (pinfunction "+_+") (pintype "passive"))
    )
    (net (code "163") (name "Net-(D28-PadA)") (class "Default")
      (node (ref "D28") (pin "A") (pinfunction "A_A") (pintype "passive"))
      (node (ref "R27") (pin "2") (pinfunction "2_2") (pintype "passive"))
    )
    (net (code "164") (name "Net-(D29-K)") (class "Default")
      (node (ref "D29") (pin "C") (pinfunction "K_C") (pintype "passive"))
      (node (ref "LED28") (pin "+") (pinfunction "+_+") (pintype "passive"))
    )
    (net (code "165") (name "Net-(D29-PadA)") (class "Default")
      (node (ref "D29") (pin "A") (pinfunction "A_A") (pintype "passive"))
      (node (ref "R28") (pin "2") (pinfunction "2_2") (pintype "passive"))
    )
    (net (code "166") (name "Net-(D30-K)") (class "Default")
      (node (ref "D30") (pin "C") (pinfunction "K_C") (pintype "passive"))
      (node (ref "LED29") (pin "+") (pinfunction "+_+") (pintype "passive"))
    )
    (net (code "167") (name "Net-(D30-PadA)") (class "Default")
      (node (ref "D30") (pin "A") (pinfunction "A_A") (pintype "passive"))
      (node (ref "R29") (pin "2") (pinfunction "2_2") (pintype "passive"))
    )
    (net (code "168") (name "Net-(D31-K)") (class "Default")
      (node (ref "D31") (pin "C") (pinfunction "K_C") (pintype "passive"))
      (node (ref "LED30") (pin "+") (pinfunction "+_+") (pintype "passive"))
    )
    (net (code "169") (name "Net-(D31-PadA)") (class "Default")
      (node (ref "D31") (pin "A") (pinfunction "A_A") (pintype "passive"))
      (node (ref "R30") (pin "2") (pinfunction "2_2") (pintype "passive"))
    )
    (net (code "170") (name "Net-(D32-K)") (class "Default")
      (node (ref "D32") (pin "C") (pinfunction "K_C") (pintype "passive"))
      (node (ref "LED31") (pin "+") (pinfunction "+_+") (pintype "passive"))
    )
    (net (code "171") (name "Net-(D32-PadA)") (class "Default")
      (node (ref "D32") (pin "A") (pinfunction "A_A") (pintype "passive"))
      (node (ref "R31") (pin "2") (pinfunction "2_2") (pintype "passive"))
    )
    (net (code "172") (name "Net-(D33-K)") (class "Default")
      (node (ref "D33") (pin "C") (pinfunction "K_C") (pintype "passive"))
      (node (ref "LED32") (pin "+") (pinfunction "+_+") (pintype "passive"))
    )
    (net (code "173") (name "Net-(D33-PadA)") (class "Default")
      (node (ref "D33") (pin "A") (pinfunction "A_A") (pintype "passive"))
      (node (ref "R32") (pin "2") (pinfunction "2_2") (pintype "passive"))
    )
    (net (code "174") (name "Net-(D34-K)") (class "Default")
      (node (ref "D34") (pin "C") (pinfunction "K_C") (pintype "passive"))
      (node (ref "LED33") (pin "+") (pinfunction "+_+") (pintype "passive"))
    )
    (net (code "175") (name "Net-(D34-PadA)") (class "Default")
      (node (ref "D34") (pin "A") (pinfunction "A_A") (pintype "passive"))
      (node (ref "R33") (pin "2") (pinfunction "2_2") (pintype "passive"))
    )
    (net (code "176") (name "Net-(D35-K)") (class "Default")
      (node (ref "D35") (pin "C") (pinfunction "K_C") (pintype "passive"))
      (node (ref "LED34") (pin "+") (pinfunction "+_+") (pintype "passive"))
    )
    (net (code "177") (name "Net-(D35-PadA)") (class "Default")
      (node (ref "D35") (pin "A") (pinfunction "A_A") (pintype "passive"))
      (node (ref "R34") (pin "2") (pinfunction "2_2") (pintype "passive"))
    )
    (net (code "178") (name "Net-(D36-K)") (class "Default")
      (node (ref "D36") (pin "C") (pinfunction "K_C") (pintype "passive"))
      (node (ref "LED35") (pin "+") (pinfunction "+_+") (pintype "passive"))
    )
    (net (code "179") (name "Net-(D36-PadA)") (class "Default")
      (node (ref "D36") (pin "A") (pinfunction "A_A") (pintype "passive"))
      (node (ref "R35") (pin "2") (pinfunction "2_2") (pintype "passive"))
    )
    (net (code "180") (name "Net-(D37-K)") (class "Default")
      (node (ref "D37") (pin "C") (pinfunction "K_C") (pintype "passive"))
      (node (ref "LED36") (pin "+") (pinfunction "+_+") (pintype "passive"))
    )
    (net (code "181") (name "Net-(D37-PadA)") (class "Default")
      (node (ref "D37") (pin "A") (pinfunction "A_A") (pintype "passive"))
      (node (ref "R36") (pin "2") (pinfunction "2_2") (pintype "passive"))
    )
    (net (code "182") (name "Net-(D38-K)") (class "Default")
      (node (ref "D38") (pin "C") (pinfunction "K_C") (pintype "passive"))
      (node (ref "LED37") (pin "+") (pinfunction "+_+") (pintype "passive"))
    )
    (net (code "183") (name "Net-(D38-PadA)") (class "Default")
      (node (ref "D38") (pin "A") (pinfunction "A_A") (pintype "passive"))
      (node (ref "R37") (pin "2") (pinfunction "2_2") (pintype "passive"))
    )
    (net (code "184") (name "Net-(D39-K)") (class "Default")
      (node (ref "D39") (pin "C") (pinfunction "K_C") (pintype "passive"))
      (node (ref "LED38") (pin "+") (pinfunction "+_+") (pintype "passive"))
    )
    (net (code "185") (name "Net-(D39-PadA)") (class "Default")
      (node (ref "D39") (pin "A") (pinfunction "A_A") (pintype "passive"))
      (node (ref "R38") (pin "2") (pinfunction "2_2") (pintype "passive"))
    )
    (net (code "186") (name "Net-(D40-K)") (class "Default")
      (node (ref "D40") (pin "C") (pinfunction "K_C") (pintype "passive"))
      (node (ref "LED39") (pin "+") (pinfunction "+_+") (pintype "passive"))
    )
    (net (code "187") (name "Net-(D40-PadA)") (class "Default")
      (node (ref "D40") (pin "A") (pinfunction "A_A") (pintype "passive"))
      (node (ref "R39") (pin "2") (pinfunction "2_2") (pintype "passive"))
    )
    (net (code "188") (name "Net-(D41-K)") (class "Default")
      (node (ref "D41") (pin "C") (pinfunction "K_C") (pintype "passive"))
      (node (ref "LED40") (pin "+") (pinfunction "+_+") (pintype "passive"))
    )
    (net (code "189") (name "Net-(D41-PadA)") (class "Default")
      (node (ref "D41") (pin "A") (pinfunction "A_A") (pintype "passive"))
      (node (ref "R40") (pin "2") (pinfunction "2_2") (pintype "passive"))
    )
    (net (code "190") (name "Net-(D42-K)") (class "Default")
      (node (ref "D42") (pin "C") (pinfunction "K_C") (pintype "passive"))
      (node (ref "LED41") (pin "+") (pinfunction "+_+") (pintype "passive"))
    )
    (net (code "191") (name "Net-(D42-PadA)") (class "Default")
      (node (ref "D42") (pin "A") (pinfunction "A_A") (pintype "passive"))
      (node (ref "R41") (pin "2") (pinfunction "2_2") (pintype "passive"))
    )
    (net (code "192") (name "Net-(D43-K)") (class "Default")
      (node (ref "D43") (pin "C") (pinfunction "K_C") (pintype "passive"))
      (node (ref "LED42") (pin "+") (pinfunction "+_+") (pintype "passive"))
    )
    (net (code "193") (name "Net-(D43-PadA)") (class "Default")
      (node (ref "D43") (pin "A") (pinfunction "A_A") (pintype "passive"))
      (node (ref "R42") (pin "2") (pinfunction "2_2") (pintype "passive"))
    )
    (net (code "194") (name "Net-(D44-K)") (class "Default")
      (node (ref "D44") (pin "C") (pinfunction "K_C") (pintype "passive"))
      (node (ref "LED43") (pin "+") (pinfunction "+_+") (pintype "passive"))
    )
    (net (code "195") (name "Net-(D44-PadA)") (class "Default")
      (node (ref "D44") (pin "A") (pinfunction "A_A") (pintype "passive"))
      (node (ref "R43") (pin "2") (pinfunction "2_2") (pintype "passive"))
    )
    (net (code "196") (name "Net-(D45-K)") (class "Default")
      (node (ref "D45") (pin "C") (pinfunction "K_C") (pintype "passive"))
      (node (ref "LED44") (pin "+") (pinfunction "+_+") (pintype "passive"))
    )
    (net (code "197") (name "Net-(D45-PadA)") (class "Default")
      (node (ref "D45") (pin "A") (pinfunction "A_A") (pintype "passive"))
      (node (ref "R44") (pin "2") (pinfunction "2_2") (pintype "passive"))
    )
    (net (code "198") (name "Net-(D46-K)") (class "Default")
      (node (ref "D46") (pin "C") (pinfunction "K_C") (pintype "passive"))
      (node (ref "LED45") (pin "+") (pinfunction "+_+") (pintype "passive"))
    )
    (net (code "199") (name "Net-(D46-PadA)") (class "Default")
      (node (ref "D46") (pin "A") (pinfunction "A_A") (pintype "passive"))
      (node (ref "R45") (pin "2") (pinfunction "2_2") (pintype "passive"))
    )
    (net (code "200") (name "Net-(D47-K)") (class "Default")
      (node (ref "D47") (pin "C") (pinfunction "K_C") (pintype "passive"))
      (node (ref "LED46") (pin "+") (pinfunction "+_+") (pintype "passive"))
    )
    (net (code "201") (name "Net-(D47-PadA)") (class "Default")
      (node (ref "D47") (pin "A") (pinfunction "A_A") (pintype "passive"))
      (node (ref "R46") (pin "2") (pinfunction "2_2") (pintype "passive"))
    )
    (net (code "202") (name "Net-(D48-K)") (class "Default")
      (node (ref "D48") (pin "C") (pinfunction "K_C") (pintype "passive"))
      (node (ref "LED47") (pin "+") (pinfunction "+_+") (pintype "passive"))
    )
    (net (code "203") (name "Net-(D48-PadA)") (class "Default")
      (node (ref "D48") (pin "A") (pinfunction "A_A") (pintype "passive"))
      (node (ref "R47") (pin "2") (pinfunction "2_2") (pintype "passive"))
    )
    (net (code "204") (name "Net-(D49-K)") (class "Default")
      (node (ref "D49") (pin "C") (pinfunction "K_C") (pintype "passive"))
      (node (ref "LED48") (pin "+") (pinfunction "+_+") (pintype "passive"))
    )
    (net (code "205") (name "Net-(D49-PadA)") (class "Default")
      (node (ref "D49") (pin "A") (pinfunction "A_A") (pintype "passive"))
      (node (ref "R48") (pin "2") (pinfunction "2_2") (pintype "passive"))
    )
    (net (code "206") (name "Net-(D146-Pad+)") (class "Default")
      (node (ref "D146") (pin "+") (pinfunction "+_+") (pintype "passive"))
      (node (ref "R115") (pin "1") (pinfunction "1_1") (pintype "passive"))
    )
    (net (code "207") (name "Net-(IC1-A0)") (class "Default")
      (node (ref "IC1") (pin "15") (pinfunction "A0_15") (pintype "input"))
      (node (ref "R108") (pin "2") (pinfunction "2_2") (pintype "passive"))
    )
    (net (code "208") (name "Net-(IC1-A1)") (class "Default")
      (node (ref "IC1") (pin "16") (pinfunction "A1_16") (pintype "input"))
      (node (ref "R109") (pin "2") (pinfunction "2_2") (pintype "passive"))
    )
    (net (code "209") (name "Net-(IC1-A2)") (class "Default")
      (node (ref "IC1") (pin "17") (pinfunction "A2_17") (pintype "input"))
      (node (ref "R110") (pin "2") (pinfunction "2_2") (pintype "passive"))
    )
    (net (code "210") (name "Net-(IC1-VDD)") (class "Default")
      (node (ref "IC1") (pin "9") (pinfunction "VDD_9") (pintype "power_in"))
      (node (ref "JMPR2") (pin "2") (pinfunction "2_2") (pintype "passive"))
    )
    (net (code "211") (name "Net-(IC4-A0)") (class "Default")
      (node (ref "IC4") (pin "15") (pinfunction "A0_15") (pintype "input"))
      (node (ref "R106") (pin "2") (pinfunction "2_2") (pintype "passive"))
    )
    (net (code "212") (name "Net-(IC4-A1)") (class "Default")
      (node (ref "IC4") (pin "16") (pinfunction "A1_16") (pintype "input"))
      (node (ref "R105") (pin "2") (pinfunction "2_2") (pintype "passive"))
    )
    (net (code "213") (name "Net-(IC4-A2)") (class "Default")
      (node (ref "IC4") (pin "17") (pinfunction "A2_17") (pintype "input"))
      (node (ref "R104") (pin "2") (pinfunction "2_2") (pintype "passive"))
    )
    (net (code "214") (name "Net-(IC4-VDD)") (class "Default")
      (node (ref "IC4") (pin "9") (pinfunction "VDD_9") (pintype "power_in"))
      (node (ref "JMPR3") (pin "2") (pinfunction "2_2") (pintype "passive"))
    )
    (net (code "215") (name "Net-(IC5-A0)") (class "Default")
      (node (ref "IC5") (pin "15") (pinfunction "A0_15") (pintype "input"))
      (node (ref "R112") (pin "2") (pinfunction "2_2") (pintype "passive"))
    )
    (net (code "216") (name "Net-(IC5-A1)") (class "Default")
      (node (ref "IC5") (pin "16") (pinfunction "A1_16") (pintype "input"))
      (node (ref "R113") (pin "2") (pinfunction "2_2") (pintype "passive"))
    )
    (net (code "217") (name "Net-(IC5-A2)") (class "Default")
      (node (ref "IC5") (pin "17") (pinfunction "A2_17") (pintype "input"))
      (node (ref "R114") (pin "2") (pinfunction "2_2") (pintype "passive"))
    )
    (net (code "218") (name "Net-(IC5-VDD)") (class "Default")
      (node (ref "IC5") (pin "9") (pinfunction "VDD_9") (pintype "power_in"))
      (node (ref "JMPR1") (pin "2") (pinfunction "2_2") (pintype "passive"))
    )
    (net (code "219") (name "Net-(J1A-S)") (class "Default")
      (node (ref "HEADER-22P1") (pin "22") (pinfunction "22_22") (pintype "bidirectional"))
      (node (ref "J1") (pin "1") (pinfunction "S_1") (pintype "passive"))
    )
    (net (code "220") (name "Net-(J1B-S)") (class "Default")
      (node (ref "HEADER-22P1") (pin "21") (pinfunction "21_21") (pintype "bidirectional"))
      (node (ref "J1") (pin "2") (pinfunction "S_2") (pintype "passive"))
    )
    (net (code "221") (name "Net-(OPTO1-A)") (class "Default")
      (node (ref "LED1") (pin "-") (pinfunction "-_-") (pintype "passive"))
      (node (ref "OPTO1") (pin "1") (pinfunction "A_1") (pintype "passive"))
      (node (ref "Z1") (pin "C") (pinfunction "C_C") (pintype "passive"))
    )
    (net (code "222") (name "Net-(OPTO2-A)") (class "Default")
      (node (ref "LED2") (pin "-") (pinfunction "-_-") (pintype "passive"))
      (node (ref "OPTO2") (pin "1") (pinfunction "A_1") (pintype "passive"))
      (node (ref "Z2") (pin "C") (pinfunction "C_C") (pintype "passive"))
    )
    (net (code "223") (name "Net-(OPTO3-A)") (class "Default")
      (node (ref "LED3") (pin "-") (pinfunction "-_-") (pintype "passive"))
      (node (ref "OPTO3") (pin "1") (pinfunction "A_1") (pintype "passive"))
      (node (ref "Z3") (pin "C") (pinfunction "C_C") (pintype "passive"))
    )
    (net (code "224") (name "Net-(OPTO4-A)") (class "Default")
      (node (ref "LED4") (pin "-") (pinfunction "-_-") (pintype "passive"))
      (node (ref "OPTO4") (pin "1") (pinfunction "A_1") (pintype "passive"))
      (node (ref "Z4") (pin "C") (pinfunction "C_C") (pintype "passive"))
    )
    (net (code "225") (name "Net-(OPTO5-A)") (class "Default")
      (node (ref "LED5") (pin "-") (pinfunction "-_-") (pintype "passive"))
      (node (ref "OPTO5") (pin "1") (pinfunction "A_1") (pintype "passive"))
      (node (ref "Z5") (pin "C") (pinfunction "C_C") (pintype "passive"))
    )
    (net (code "226") (name "Net-(OPTO6-A)") (class "Default")
      (node (ref "LED6") (pin "-") (pinfunction "-_-") (pintype "passive"))
      (node (ref "OPTO6") (pin "1") (pinfunction "A_1") (pintype "passive"))
      (node (ref "Z6") (pin "C") (pinfunction "C_C") (pintype "passive"))
    )
    (net (code "227") (name "Net-(OPTO7-A)") (class "Default")
      (node (ref "LED7") (pin "-") (pinfunction "-_-") (pintype "passive"))
      (node (ref "OPTO7") (pin "1") (pinfunction "A_1") (pintype "passive"))
      (node (ref "Z7") (pin "C") (pinfunction "C_C") (pintype "passive"))
    )
    (net (code "228") (name "Net-(OPTO8-A)") (class "Default")
      (node (ref "LED8") (pin "-") (pinfunction "-_-") (pintype "passive"))
      (node (ref "OPTO8") (pin "1") (pinfunction "A_1") (pintype "passive"))
      (node (ref "Z8") (pin "C") (pinfunction "C_C") (pintype "passive"))
    )
    (net (code "229") (name "Net-(OPTO9-A)") (class "Default")
      (node (ref "LED9") (pin "-") (pinfunction "-_-") (pintype "passive"))
      (node (ref "OPTO9") (pin "1") (pinfunction "A_1") (pintype "passive"))
      (node (ref "Z9") (pin "C") (pinfunction "C_C") (pintype "passive"))
    )
    (net (code "230") (name "Net-(OPTO10-A)") (class "Default")
      (node (ref "LED10") (pin "-") (pinfunction "-_-") (pintype "passive"))
      (node (ref "OPTO10") (pin "1") (pinfunction "A_1") (pintype "passive"))
      (node (ref "Z10") (pin "C") (pinfunction "C_C") (pintype "passive"))
    )
    (net (code "231") (name "Net-(OPTO11-A)") (class "Default")
      (node (ref "LED11") (pin "-") (pinfunction "-_-") (pintype "passive"))
      (node (ref "OPTO11") (pin "1") (pinfunction "A_1") (pintype "passive"))
      (node (ref "Z11") (pin "C") (pinfunction "C_C") (pintype "passive"))
    )
    (net (code "232") (name "Net-(OPTO12-A)") (class "Default")
      (node (ref "LED12") (pin "-") (pinfunction "-_-") (pintype "passive"))
      (node (ref "OPTO12") (pin "1") (pinfunction "A_1") (pintype "passive"))
      (node (ref "Z12") (pin "C") (pinfunction "C_C") (pintype "passive"))
    )
    (net (code "233") (name "Net-(OPTO13-A)") (class "Default")
      (node (ref "LED13") (pin "-") (pinfunction "-_-") (pintype "passive"))
      (node (ref "OPTO13") (pin "1") (pinfunction "A_1") (pintype "passive"))
      (node (ref "Z13") (pin "C") (pinfunction "C_C") (pintype "passive"))
    )
    (net (code "234") (name "Net-(OPTO14-A)") (class "Default")
      (node (ref "LED14") (pin "-") (pinfunction "-_-") (pintype "passive"))
      (node (ref "OPTO14") (pin "1") (pinfunction "A_1") (pintype "passive"))
      (node (ref "Z14") (pin "C") (pinfunction "C_C") (pintype "passive"))
    )
    (net (code "235") (name "Net-(OPTO15-A)") (class "Default")
      (node (ref "LED15") (pin "-") (pinfunction "-_-") (pintype "passive"))
      (node (ref "OPTO15") (pin "1") (pinfunction "A_1") (pintype "passive"))
      (node (ref "Z15") (pin "C") (pinfunction "C_C") (pintype "passive"))
    )
    (net (code "236") (name "Net-(OPTO16-A)") (class "Default")
      (node (ref "LED16") (pin "-") (pinfunction "-_-") (pintype "passive"))
      (node (ref "OPTO16") (pin "1") (pinfunction "A_1") (pintype "passive"))
      (node (ref "Z16") (pin "C") (pinfunction "C_C") (pintype "passive"))
    )
    (net (code "237") (name "Net-(OPTO17-A)") (class "Default")
      (node (ref "LED17") (pin "-") (pinfunction "-_-") (pintype "passive"))
      (node (ref "OPTO17") (pin "1") (pinfunction "A_1") (pintype "passive"))
      (node (ref "Z17") (pin "C") (pinfunction "C_C") (pintype "passive"))
    )
    (net (code "238") (name "Net-(OPTO18-A)") (class "Default")
      (node (ref "LED18") (pin "-") (pinfunction "-_-") (pintype "passive"))
      (node (ref "OPTO18") (pin "1") (pinfunction "A_1") (pintype "passive"))
      (node (ref "Z18") (pin "C") (pinfunction "C_C") (pintype "passive"))
    )
    (net (code "239") (name "Net-(OPTO19-A)") (class "Default")
      (node (ref "LED19") (pin "-") (pinfunction "-_-") (pintype "passive"))
      (node (ref "OPTO19") (pin "1") (pinfunction "A_1") (pintype "passive"))
      (node (ref "Z19") (pin "C") (pinfunction "C_C") (pintype "passive"))
    )
    (net (code "240") (name "Net-(OPTO20-A)") (class "Default")
      (node (ref "LED20") (pin "-") (pinfunction "-_-") (pintype "passive"))
      (node (ref "OPTO20") (pin "1") (pinfunction "A_1") (pintype "passive"))
      (node (ref "Z20") (pin "C") (pinfunction "C_C") (pintype "passive"))
    )
    (net (code "241") (name "Net-(OPTO21-A)") (class "Default")
      (node (ref "LED21") (pin "-") (pinfunction "-_-") (pintype "passive"))
      (node (ref "OPTO21") (pin "1") (pinfunction "A_1") (pintype "passive"))
      (node (ref "Z21") (pin "C") (pinfunction "C_C") (pintype "passive"))
    )
    (net (code "242") (name "Net-(OPTO22-A)") (class "Default")
      (node (ref "LED22") (pin "-") (pinfunction "-_-") (pintype "passive"))
      (node (ref "OPTO22") (pin "1") (pinfunction "A_1") (pintype "passive"))
      (node (ref "Z22") (pin "C") (pinfunction "C_C") (pintype "passive"))
    )
    (net (code "243") (name "Net-(OPTO23-A)") (class "Default")
      (node (ref "LED23") (pin "-") (pinfunction "-_-") (pintype "passive"))
      (node (ref "OPTO23") (pin "1") (pinfunction "A_1") (pintype "passive"))
      (node (ref "Z23") (pin "C") (pinfunction "C_C") (pintype "passive"))
    )
    (net (code "244") (name "Net-(OPTO24-A)") (class "Default")
      (node (ref "LED24") (pin "-") (pinfunction "-_-") (pintype "passive"))
      (node (ref "OPTO24") (pin "1") (pinfunction "A_1") (pintype "passive"))
      (node (ref "Z24") (pin "C") (pinfunction "C_C") (pintype "passive"))
    )
    (net (code "245") (name "Net-(OPTO25-A)") (class "Default")
      (node (ref "LED25") (pin "-") (pinfunction "-_-") (pintype "passive"))
      (node (ref "OPTO25") (pin "1") (pinfunction "A_1") (pintype "passive"))
      (node (ref "Z25") (pin "C") (pinfunction "C_C") (pintype "passive"))
    )
    (net (code "246") (name "Net-(OPTO26-A)") (class "Default")
      (node (ref "LED26") (pin "-") (pinfunction "-_-") (pintype "passive"))
      (node (ref "OPTO26") (pin "1") (pinfunction "A_1") (pintype "passive"))
      (node (ref "Z26") (pin "C") (pinfunction "C_C") (pintype "passive"))
    )
    (net (code "247") (name "Net-(OPTO27-A)") (class "Default")
      (node (ref "LED27") (pin "-") (pinfunction "-_-") (pintype "passive"))
      (node (ref "OPTO27") (pin "1") (pinfunction "A_1") (pintype "passive"))
      (node (ref "Z27") (pin "C") (pinfunction "C_C") (pintype "passive"))
    )
    (net (code "248") (name "Net-(OPTO28-A)") (class "Default")
      (node (ref "LED28") (pin "-") (pinfunction "-_-") (pintype "passive"))
      (node (ref "OPTO28") (pin "1") (pinfunction "A_1") (pintype "passive"))
      (node (ref "Z28") (pin "C") (pinfunction "C_C") (pintype "passive"))
    )
    (net (code "249") (name "Net-(OPTO29-A)") (class "Default")
      (node (ref "LED29") (pin "-") (pinfunction "-_-") (pintype "passive"))
      (node (ref "OPTO29") (pin "1") (pinfunction "A_1") (pintype "passive"))
      (node (ref "Z29") (pin "C") (pinfunction "C_C") (pintype "passive"))
    )
    (net (code "250") (name "Net-(OPTO30-A)") (class "Default")
      (node (ref "LED30") (pin "-") (pinfunction "-_-") (pintype "passive"))
      (node (ref "OPTO30") (pin "1") (pinfunction "A_1") (pintype "passive"))
      (node (ref "Z30") (pin "C") (pinfunction "C_C") (pintype "passive"))
    )
    (net (code "251") (name "Net-(OPTO31-A)") (class "Default")
      (node (ref "LED31") (pin "-") (pinfunction "-_-") (pintype "passive"))
      (node (ref "OPTO31") (pin "1") (pinfunction "A_1") (pintype "passive"))
      (node (ref "Z31") (pin "C") (pinfunction "C_C") (pintype "passive"))
    )
    (net (code "252") (name "Net-(OPTO32-A)") (class "Default")
      (node (ref "LED32") (pin "-") (pinfunction "-_-") (pintype "passive"))
      (node (ref "OPTO32") (pin "1") (pinfunction "A_1") (pintype "passive"))
      (node (ref "Z32") (pin "C") (pinfunction "C_C") (pintype "passive"))
    )
    (net (code "253") (name "Net-(OPTO33-A)") (class "Default")
      (node (ref "LED33") (pin "-") (pinfunction "-_-") (pintype "passive"))
      (node (ref "OPTO33") (pin "1") (pinfunction "A_1") (pintype "passive"))
      (node (ref "Z33") (pin "C") (pinfunction "C_C") (pintype "passive"))
    )
    (net (code "254") (name "Net-(OPTO34-A)") (class "Default")
      (node (ref "LED34") (pin "-") (pinfunction "-_-") (pintype "passive"))
      (node (ref "OPTO34") (pin "1") (pinfunction "A_1") (pintype "passive"))
      (node (ref "Z34") (pin "C") (pinfunction "C_C") (pintype "passive"))
    )
    (net (code "255") (name "Net-(OPTO35-A)") (class "Default")
      (node (ref "LED35") (pin "-") (pinfunction "-_-") (pintype "passive"))
      (node (ref "OPTO35") (pin "1") (pinfunction "A_1") (pintype "passive"))
      (node (ref "Z35") (pin "C") (pinfunction "C_C") (pintype "passive"))
    )
    (net (code "256") (name "Net-(OPTO36-A)") (class "Default")
      (node (ref "LED36") (pin "-") (pinfunction "-_-") (pintype "passive"))
      (node (ref "OPTO36") (pin "1") (pinfunction "A_1") (pintype "passive"))
      (node (ref "Z36") (pin "C") (pinfunction "C_C") (pintype "passive"))
    )
    (net (code "257") (name "Net-(OPTO37-A)") (class "Default")
      (node (ref "LED37") (pin "-") (pinfunction "-_-") (pintype "passive"))
      (node (ref "OPTO37") (pin "1") (pinfunction "A_1") (pintype "passive"))
      (node (ref "Z37") (pin "C") (pinfunction "C_C") (pintype "passive"))
    )
    (net (code "258") (name "Net-(OPTO38-A)") (class "Default")
      (node (ref "LED38") (pin "-") (pinfunction "-_-") (pintype "passive"))
      (node (ref "OPTO38") (pin "1") (pinfunction "A_1") (pintype "passive"))
      (node (ref "Z38") (pin "C") (pinfunction "C_C") (pintype "passive"))
    )
    (net (code "259") (name "Net-(OPTO39-A)") (class "Default")
      (node (ref "LED39") (pin "-") (pinfunction "-_-") (pintype "passive"))
      (node (ref "OPTO39") (pin "1") (pinfunction "A_1") (pintype "passive"))
      (node (ref "Z39") (pin "C") (pinfunction "C_C") (pintype "passive"))
    )
    (net (code "260") (name "Net-(OPTO40-A)") (class "Default")
      (node (ref "LED40") (pin "-") (pinfunction "-_-") (pintype "passive"))
      (node (ref "OPTO40") (pin "1") (pinfunction "A_1") (pintype "passive"))
      (node (ref "Z40") (pin "C") (pinfunction "C_C") (pintype "passive"))
    )
    (net (code "261") (name "Net-(OPTO41-A)") (class "Default")
      (node (ref "LED41") (pin "-") (pinfunction "-_-") (pintype "passive"))
      (node (ref "OPTO41") (pin "1") (pinfunction "A_1") (pintype "passive"))
      (node (ref "Z41") (pin "C") (pinfunction "C_C") (pintype "passive"))
    )
    (net (code "262") (name "Net-(OPTO42-A)") (class "Default")
      (node (ref "LED42") (pin "-") (pinfunction "-_-") (pintype "passive"))
      (node (ref "OPTO42") (pin "1") (pinfunction "A_1") (pintype "passive"))
      (node (ref "Z42") (pin "C") (pinfunction "C_C") (pintype "passive"))
    )
    (net (code "263") (name "Net-(OPTO43-A)") (class "Default")
      (node (ref "LED43") (pin "-") (pinfunction "-_-") (pintype "passive"))
      (node (ref "OPTO43") (pin "1") (pinfunction "A_1") (pintype "passive"))
      (node (ref "Z43") (pin "C") (pinfunction "C_C") (pintype "passive"))
    )
    (net (code "264") (name "Net-(OPTO44-A)") (class "Default")
      (node (ref "LED44") (pin "-") (pinfunction "-_-") (pintype "passive"))
      (node (ref "OPTO44") (pin "1") (pinfunction "A_1") (pintype "passive"))
      (node (ref "Z44") (pin "C") (pinfunction "C_C") (pintype "passive"))
    )
    (net (code "265") (name "Net-(OPTO45-A)") (class "Default")
      (node (ref "LED45") (pin "-") (pinfunction "-_-") (pintype "passive"))
      (node (ref "OPTO45") (pin "1") (pinfunction "A_1") (pintype "passive"))
      (node (ref "Z45") (pin "C") (pinfunction "C_C") (pintype "passive"))
    )
    (net (code "266") (name "Net-(OPTO46-A)") (class "Default")
      (node (ref "LED46") (pin "-") (pinfunction "-_-") (pintype "passive"))
      (node (ref "OPTO46") (pin "1") (pinfunction "A_1") (pintype "passive"))
      (node (ref "Z46") (pin "C") (pinfunction "C_C") (pintype "passive"))
    )
    (net (code "267") (name "Net-(OPTO47-A)") (class "Default")
      (node (ref "LED47") (pin "-") (pinfunction "-_-") (pintype "passive"))
      (node (ref "OPTO47") (pin "1") (pinfunction "A_1") (pintype "passive"))
      (node (ref "Z47") (pin "C") (pinfunction "C_C") (pintype "passive"))
    )
    (net (code "268") (name "Net-(OPTO48-A)") (class "Default")
      (node (ref "LED48") (pin "-") (pinfunction "-_-") (pintype "passive"))
      (node (ref "OPTO48") (pin "1") (pinfunction "A_1") (pintype "passive"))
      (node (ref "Z48") (pin "C") (pinfunction "C_C") (pintype "passive"))
    )
    (net (code "269") (name "Net-(Q1-B)") (class "Default")
      (node (ref "Q1") (pin "1") (pinfunction "B_1") (pintype "passive"))
      (node (ref "U49") (pin "3") (pinfunction "ET_3") (pintype "passive"))
    )
    (net (code "270") (name "Net-(Q1-C)") (class "Default")
      (node (ref "D1") (pin "A") (pinfunction "A_A") (pintype "passive"))
      (node (ref "K1") (pin "A2") (pinfunction "A2_A2") (pintype "passive"))
      (node (ref "Q1") (pin "3") (pinfunction "C_3") (pintype "passive"))
    )
    (net (code "271") (name "Net-(U49-A)") (class "Default")
      (node (ref "D146") (pin "-") (pinfunction "-_-") (pintype "passive"))
      (node (ref "U49") (pin "1") (pinfunction "A_1") (pintype "passive"))
    )
    (net (code "272") (name "Net-(U49-CT)") (class "Default")
      (node (ref "R116") (pin "1") (pinfunction "1_1") (pintype "passive"))
      (node (ref "U49") (pin "4") (pinfunction "CT_4") (pintype "passive"))
    )
    (net (code "273") (name "RELAY") (class "Default")
      (node (ref "R115") (pin "2") (pinfunction "2_2") (pintype "passive"))
      (node (ref "SV1") (pin "1") (pinfunction "1_1") (pintype "passive"))
    )
    (net (code "274") (name "VCC") (class "Default")
      (node (ref "D1") (pin "C") (pinfunction "K_C") (pintype "passive"))
      (node (ref "JMPR1") (pin "1") (pinfunction "1_1") (pintype "passive"))
      (node (ref "JMPR2") (pin "1") (pinfunction "1_1") (pintype "passive"))
      (node (ref "JMPR3") (pin "1") (pinfunction "1_1") (pintype "passive"))
      (node (ref "JP2") (pin "1") (pinfunction "1_1") (pintype "passive"))
      (node (ref "JP2") (pin "3") (pinfunction "3_3") (pintype "passive"))
      (node (ref "JP2") (pin "5") (pinfunction "5_5") (pintype "passive"))
      (node (ref "JP2") (pin "7") (pinfunction "7_7") (pintype "passive"))
      (node (ref "K1") (pin "A1") (pinfunction "A1_A1") (pintype "passive"))
      (node (ref "R100") (pin "2") (pinfunction "2_2") (pintype "passive"))
      (node (ref "R101") (pin "2") (pinfunction "2_2") (pintype "passive"))
      (node (ref "R102") (pin "2") (pinfunction "2_2") (pintype "passive"))
      (node (ref "R103") (pin "1") (pinfunction "1_1") (pintype "passive"))
      (node (ref "R107") (pin "2") (pinfunction "2_2") (pintype "passive"))
      (node (ref "R108") (pin "1") (pinfunction "1_1") (pintype "passive"))
      (node (ref "R111") (pin "1") (pinfunction "1_1") (pintype "passive"))
      (node (ref "R113") (pin "1") (pinfunction "1_1") (pintype "passive"))
      (node (ref "R116") (pin "2") (pinfunction "2_2") (pintype "passive"))
      (node (ref "R49") (pin "2") (pinfunction "2_2") (pintype "passive"))
      (node (ref "R50") (pin "2") (pinfunction "2_2") (pintype "passive"))
      (node (ref "R51") (pin "2") (pinfunction "2_2") (pintype "passive"))
      (node (ref "R52") (pin "2") (pinfunction "2_2") (pintype "passive"))
      (node (ref "R53") (pin "2") (pinfunction "2_2") (pintype "passive"))
      (node (ref "R54") (pin "2") (pinfunction "2_2") (pintype "passive"))
      (node (ref "R55") (pin "2") (pinfunction "2_2") (pintype "passive"))
      (node (ref "R56") (pin "2") (pinfunction "2_2") (pintype "passive"))
      (node (ref "R57") (pin "2") (pinfunction "2_2") (pintype "passive"))
      (node (ref "R58") (pin "2") (pinfunction "2_2") (pintype "passive"))
      (node (ref "R59") (pin "2") (pinfunction "2_2") (pintype "passive"))
      (node (ref "R60") (pin "2") (pinfunction "2_2") (pintype "passive"))
      (node (ref "R61") (pin "2") (pinfunction "2_2") (pintype "passive"))
      (node (ref "R62") (pin "2") (pinfunction "2_2") (pintype "passive"))
      (node (ref "R63") (pin "2") (pinfunction "2_2") (pintype "passive"))
      (node (ref "R64") (pin "2") (pinfunction "2_2") (pintype "passive"))
      (node (ref "R65") (pin "2") (pinfunction "2_2") (pintype "passive"))
      (node (ref "R66") (pin "2") (pinfunction "2_2") (pintype "passive"))
      (node (ref "R67") (pin "2") (pinfunction "2_2") (pintype "passive"))
      (node (ref "R68") (pin "2") (pinfunction "2_2") (pintype "passive"))
      (node (ref "R69") (pin "2") (pinfunction "2_2") (pintype "passive"))
      (node (ref "R70") (pin "2") (pinfunction "2_2") (pintype "passive"))
      (node (ref "R71") (pin "2") (pinfunction "2_2") (pintype "passive"))
      (node (ref "R72") (pin "2") (pinfunction "2_2") (pintype "passive"))
      (node (ref "R73") (pin "2") (pinfunction "2_2") (pintype "passive"))
      (node (ref "R74") (pin "2") (pinfunction "2_2") (pintype "passive"))
      (node (ref "R75") (pin "2") (pinfunction "2_2") (pintype "passive"))
      (node (ref "R76") (pin "2") (pinfunction "2_2") (pintype "passive"))
      (node (ref "R77") (pin "2") (pinfunction "2_2") (pintype "passive"))
      (node (ref "R78") (pin "2") (pinfunction "2_2") (pintype "passive"))
      (node (ref "R79") (pin "2") (pinfunction "2_2") (pintype "passive"))
      (node (ref "R80") (pin "2") (pinfunction "2_2") (pintype "passive"))
      (node (ref "R81") (pin "2") (pinfunction "2_2") (pintype "passive"))
      (node (ref "R82") (pin "2") (pinfunction "2_2") (pintype "passive"))
      (node (ref "R83") (pin "2") (pinfunction "2_2") (pintype "passive"))
      (node (ref "R84") (pin "2") (pinfunction "2_2") (pintype "passive"))
      (node (ref "R85") (pin "2") (pinfunction "2_2") (pintype "passive"))
      (node (ref "R86") (pin "2") (pinfunction "2_2") (pintype "passive"))
      (node (ref "R87") (pin "2") (pinfunction "2_2") (pintype "passive"))
      (node (ref "R88") (pin "2") (pinfunction "2_2") (pintype "passive"))
      (node (ref "R89") (pin "2") (pinfunction "2_2") (pintype "passive"))
      (node (ref "R90") (pin "2") (pinfunction "2_2") (pintype "passive"))
      (node (ref "R91") (pin "2") (pinfunction "2_2") (pintype "passive"))
      (node (ref "R92") (pin "2") (pinfunction "2_2") (pintype "passive"))
      (node (ref "R93") (pin "2") (pinfunction "2_2") (pintype "passive"))
      (node (ref "R94") (pin "2") (pinfunction "2_2") (pintype "passive"))
      (node (ref "R95") (pin "2") (pinfunction "2_2") (pintype "passive"))
      (node (ref "R96") (pin "2") (pinfunction "2_2") (pintype "passive"))
      (node (ref "R97") (pin "2") (pinfunction "2_2") (pintype "passive"))
      (node (ref "R98") (pin "2") (pinfunction "2_2") (pintype "passive"))
      (node (ref "R99") (pin "2") (pinfunction "2_2") (pintype "passive"))
      (node (ref "SV1") (pin "9") (pinfunction "9_9") (pintype "passive"))
      (node (ref "TTL-RS1") (pin "VCC") (pinfunction "VCC_VCC") (pintype "bidirectional"))
    )
    (net (code "275") (name "unconnected-(IC1-INTA-Pad20)") (class "Default")
      (node (ref "IC1") (pin "20") (pinfunction "INTA_20") (pintype "output"))
    )
    (net (code "276") (name "unconnected-(IC1-INTB-Pad19)") (class "Default")
      (node (ref "IC1") (pin "19") (pinfunction "INTB_19") (pintype "output"))
    )
    (net (code "277") (name "unconnected-(IC4-INTA-Pad20)") (class "Default")
      (node (ref "IC4") (pin "20") (pinfunction "INTA_20") (pintype "output"))
    )
    (net (code "278") (name "unconnected-(IC4-INTB-Pad19)") (class "Default")
      (node (ref "IC4") (pin "19") (pinfunction "INTB_19") (pintype "output"))
    )
    (net (code "279") (name "unconnected-(IC5-INTA-Pad20)") (class "Default")
      (node (ref "IC5") (pin "20") (pinfunction "INTA_20") (pintype "output"))
    )
    (net (code "280") (name "unconnected-(IC5-INTB-Pad19)") (class "Default")
      (node (ref "IC5") (pin "19") (pinfunction "INTB_19") (pintype "output"))
    )
  )
)
